# ALU.net
KiCad netlist of a schematic drawn in EAGLE
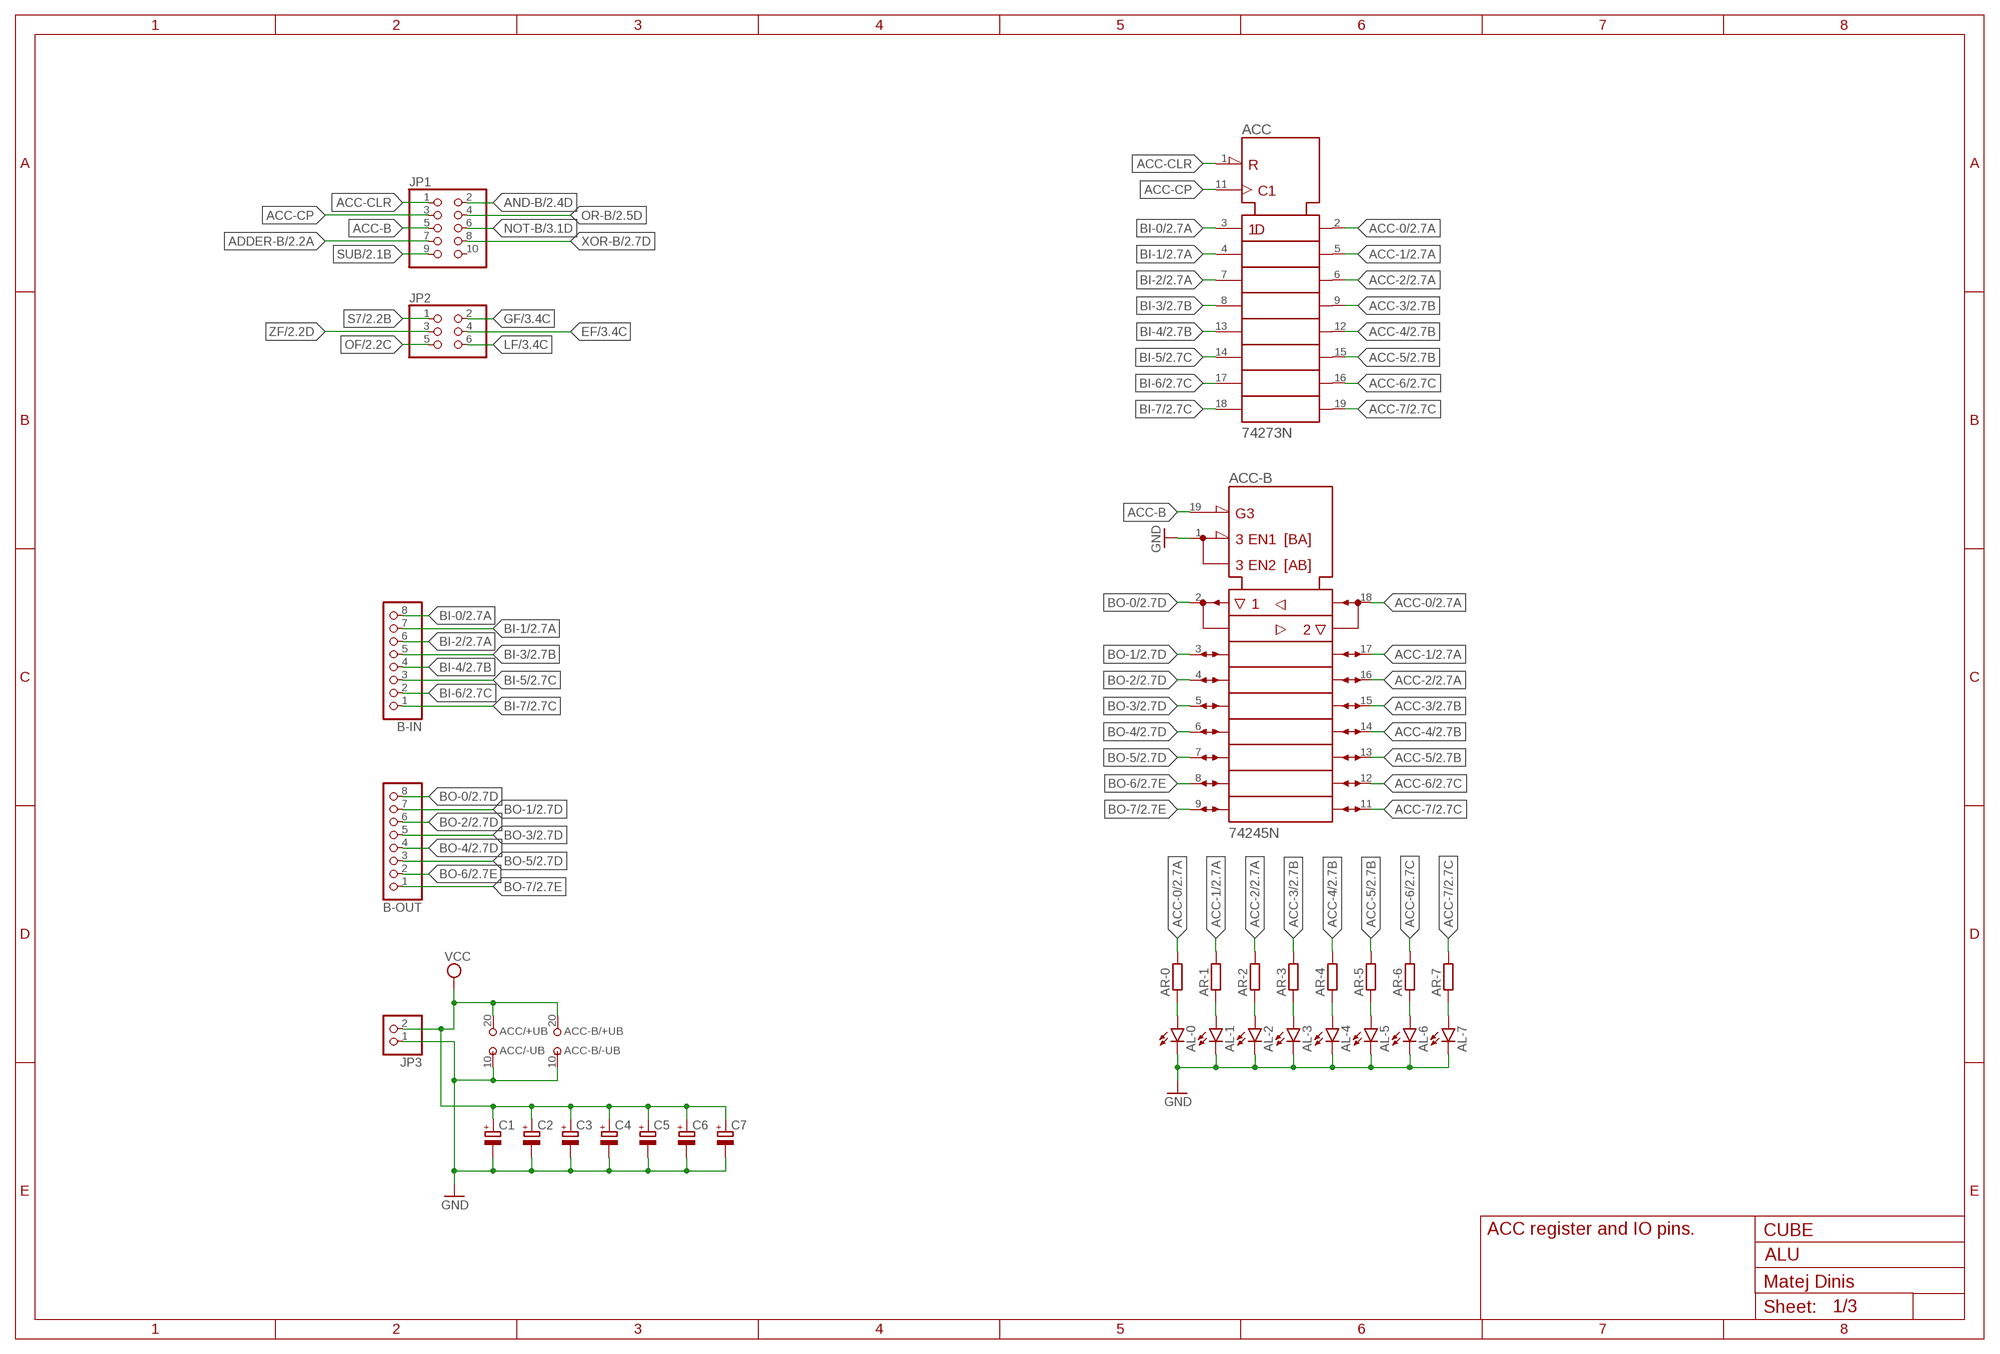
[diagram p0: schematic, sheet 1]
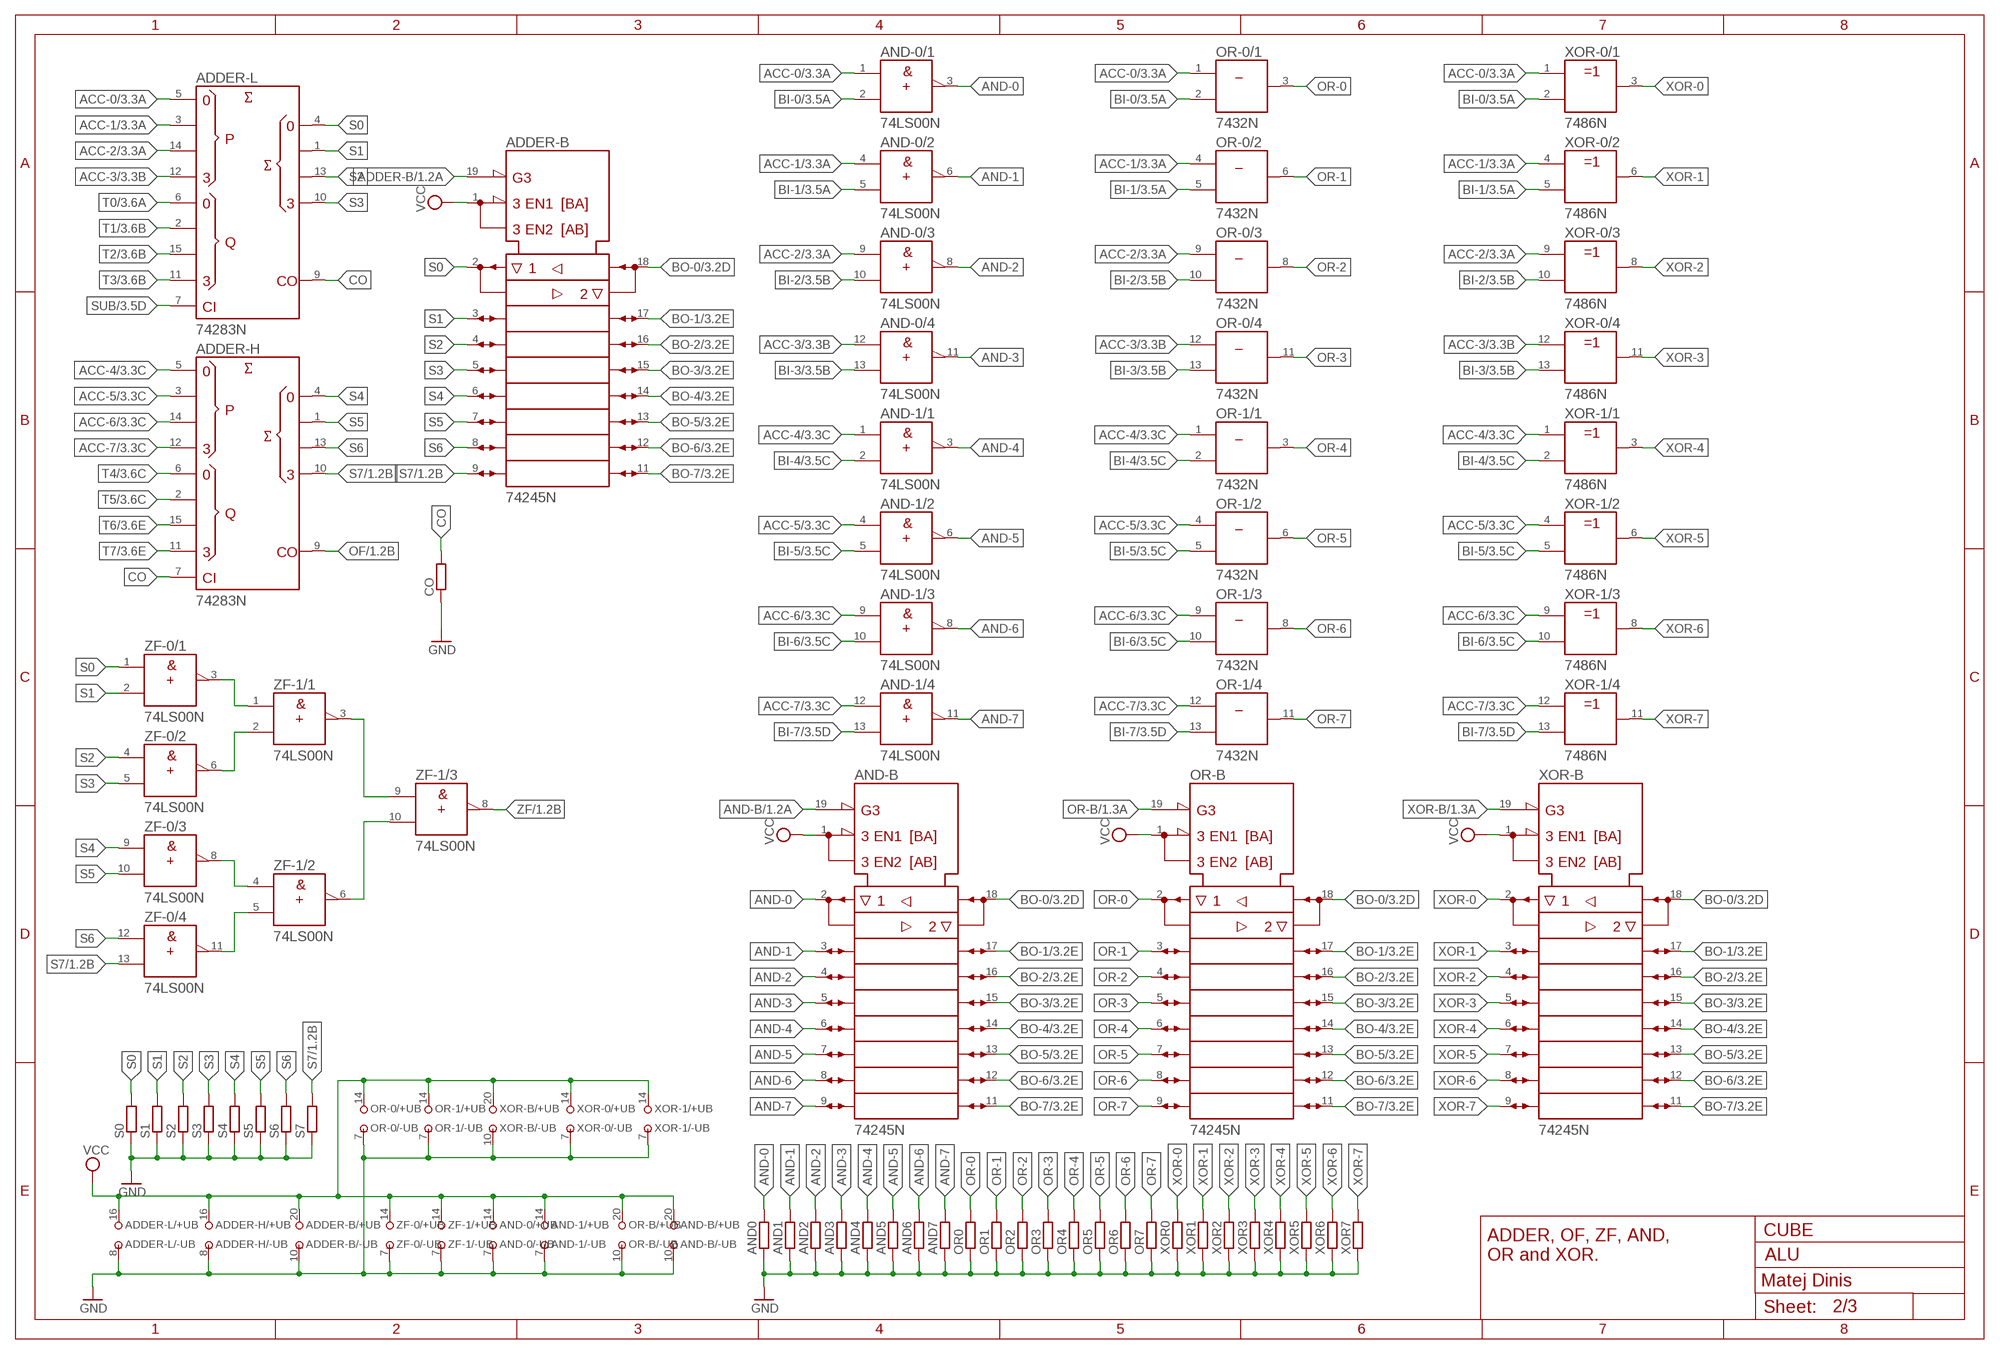
[diagram p1: schematic, sheet 2]
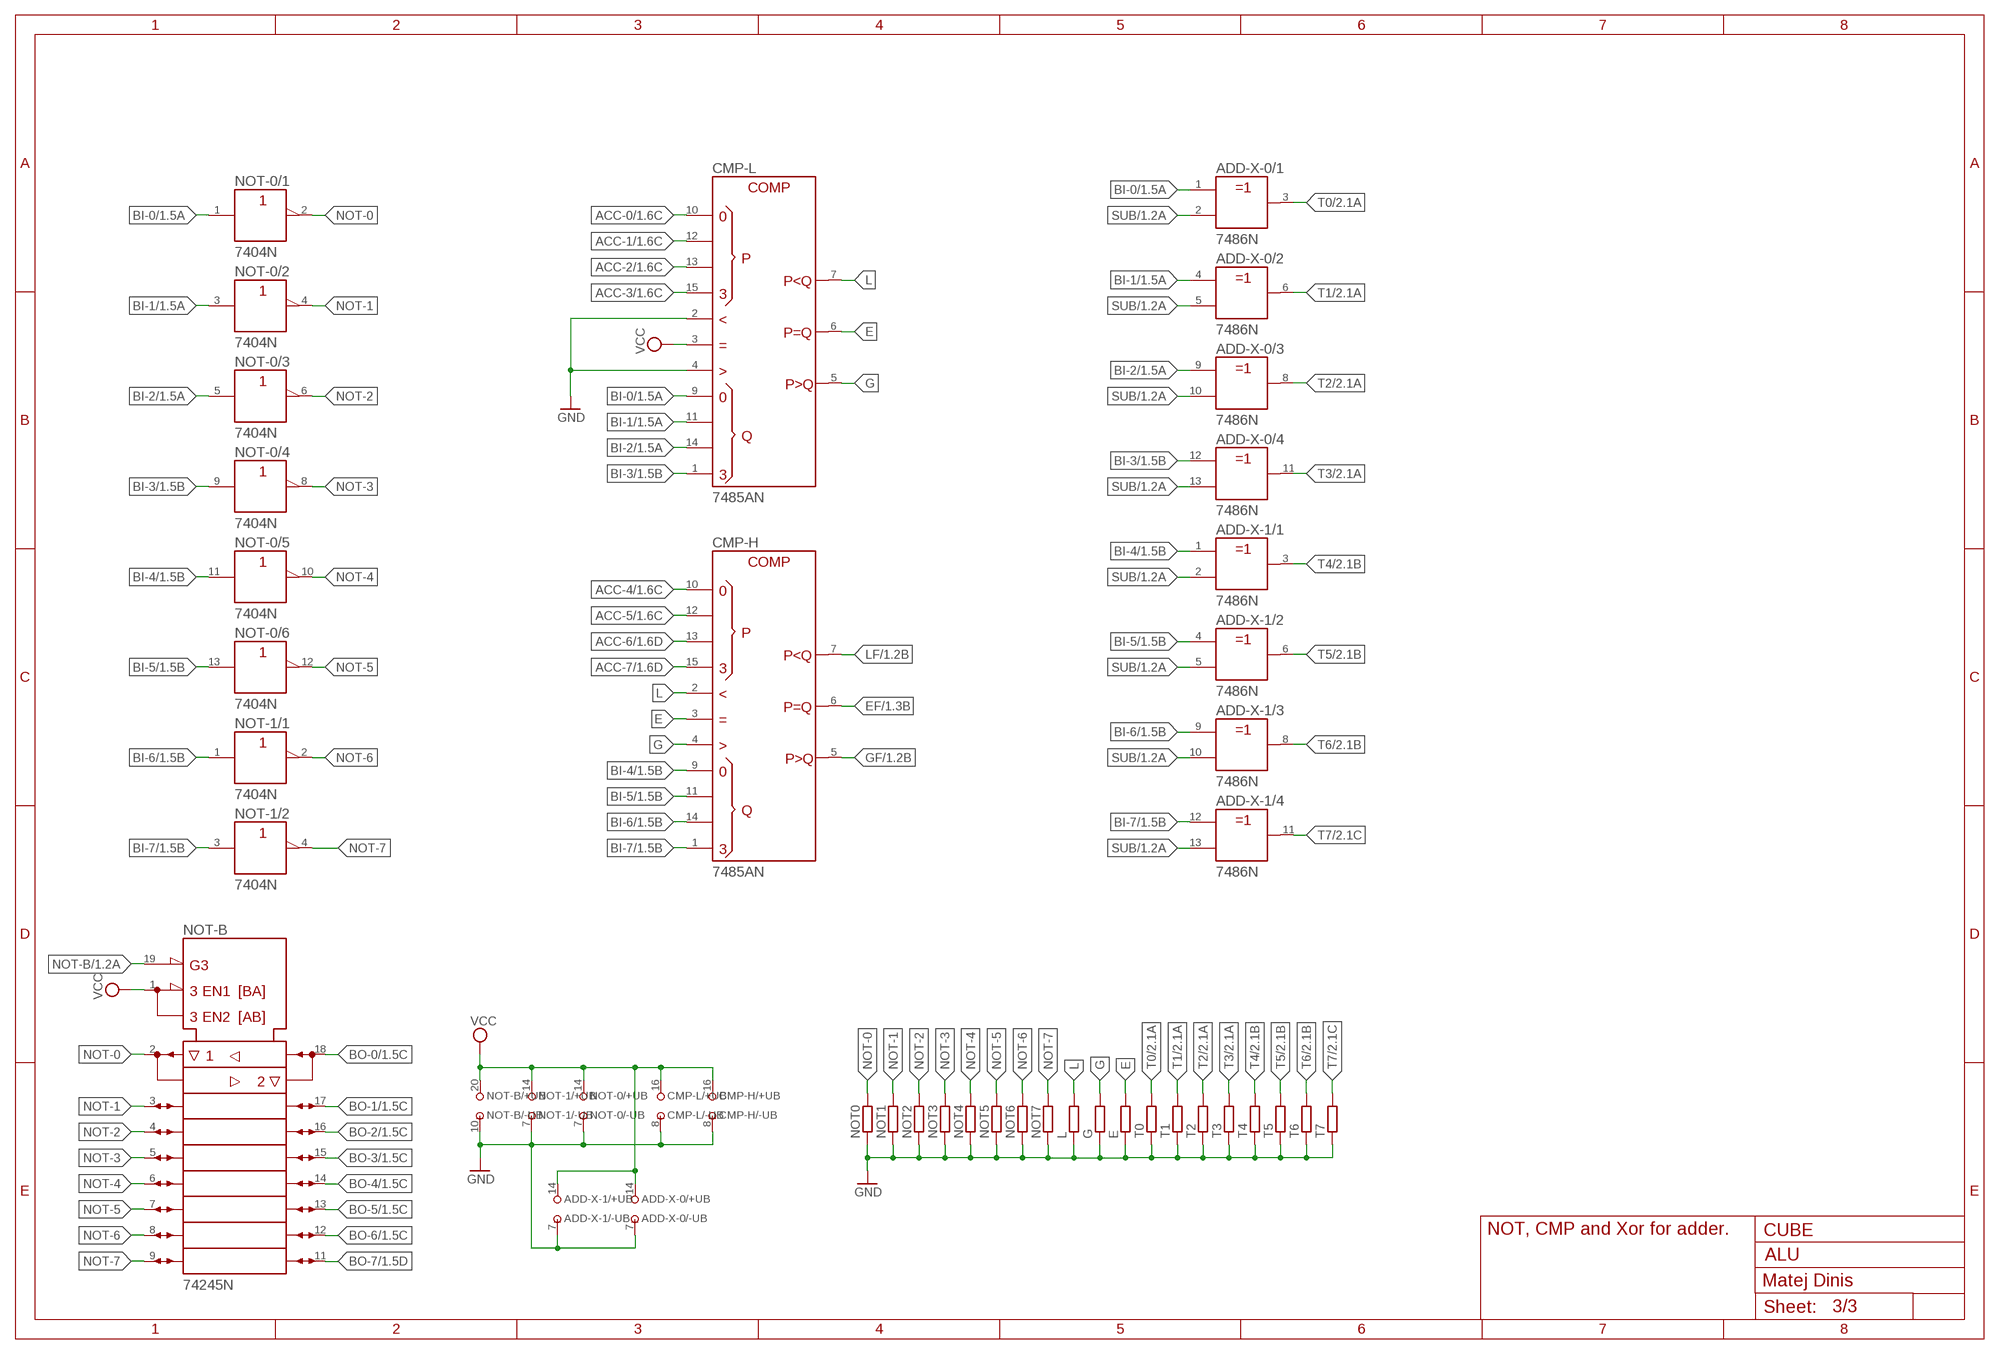
[diagram p2: schematic, sheet 3]

(export (version "E")
  (design (tool "Eeschema 10.0.6"))
  (components
    (comp (ref "ADDER-B")
      (value "74245N")
      (footprint "eagle-import:DIL20")
      (libsource (lib "eagle-import") (part "74245N"))
    )
    (comp (ref "ADDER-H")
      (value "74283N")
      (footprint "eagle-import:DIL16")
      (libsource (lib "eagle-import") (part "74283N"))
    )
    (comp (ref "ADDER-L")
      (value "74283N")
      (footprint "eagle-import:DIL16")
      (libsource (lib "eagle-import") (part "74283N"))
    )
    (comp (ref "AND-0")
      (value "74LS00N")
      (footprint "eagle-import:DIL14")
      (libsource (lib "eagle-import") (part "7400NLS"))
    )
    (comp (ref "AND-1")
      (value "74LS00N")
      (footprint "eagle-import:DIL14")
      (libsource (lib "eagle-import") (part "7400NLS"))
    )
    (comp (ref "AND-B")
      (value "74245N")
      (footprint "eagle-import:DIL20")
      (libsource (lib "eagle-import") (part "74245N"))
    )
    (comp (ref "AND0")
      (value "R-EU_0207/10")
      (footprint "eagle-import:0207_10")
      (libsource (lib "eagle-import") (part "R-EU_0207/10"))
    )
    (comp (ref "AND1")
      (value "R-EU_0207/10")
      (footprint "eagle-import:0207_10")
      (libsource (lib "eagle-import") (part "R-EU_0207/10"))
    )
    (comp (ref "AND2")
      (value "R-EU_0207/10")
      (footprint "eagle-import:0207_10")
      (libsource (lib "eagle-import") (part "R-EU_0207/10"))
    )
    (comp (ref "AND3")
      (value "R-EU_0207/10")
      (footprint "eagle-import:0207_10")
      (libsource (lib "eagle-import") (part "R-EU_0207/10"))
    )
    (comp (ref "AND4")
      (value "R-EU_0207/10")
      (footprint "eagle-import:0207_10")
      (libsource (lib "eagle-import") (part "R-EU_0207/10"))
    )
    (comp (ref "AND5")
      (value "R-EU_0207/10")
      (footprint "eagle-import:0207_10")
      (libsource (lib "eagle-import") (part "R-EU_0207/10"))
    )
    (comp (ref "AND6")
      (value "R-EU_0207/10")
      (footprint "eagle-import:0207_10")
      (libsource (lib "eagle-import") (part "R-EU_0207/10"))
    )
    (comp (ref "AND7")
      (value "R-EU_0207/10")
      (footprint "eagle-import:0207_10")
      (libsource (lib "eagle-import") (part "R-EU_0207/10"))
    )
    (comp (ref "CO")
      (value "R-EU_0207/10")
      (footprint "eagle-import:0207_10")
      (libsource (lib "eagle-import") (part "R-EU_0207/10"))
    )
    (comp (ref "OR-0")
      (value "7432N")
      (footprint "eagle-import:DIL14")
      (libsource (lib "eagle-import") (part "7432N"))
    )
    (comp (ref "OR-1")
      (value "7432N")
      (footprint "eagle-import:DIL14")
      (libsource (lib "eagle-import") (part "7432N"))
    )
    (comp (ref "OR-B")
      (value "74245N")
      (footprint "eagle-import:DIL20")
      (libsource (lib "eagle-import") (part "74245N"))
    )
    (comp (ref "OR0")
      (value "R-EU_0207/10")
      (footprint "eagle-import:0207_10")
      (libsource (lib "eagle-import") (part "R-EU_0207/10"))
    )
    (comp (ref "OR1")
      (value "R-EU_0207/10")
      (footprint "eagle-import:0207_10")
      (libsource (lib "eagle-import") (part "R-EU_0207/10"))
    )
    (comp (ref "OR2")
      (value "R-EU_0207/10")
      (footprint "eagle-import:0207_10")
      (libsource (lib "eagle-import") (part "R-EU_0207/10"))
    )
    (comp (ref "OR3")
      (value "R-EU_0207/10")
      (footprint "eagle-import:0207_10")
      (libsource (lib "eagle-import") (part "R-EU_0207/10"))
    )
    (comp (ref "OR4")
      (value "R-EU_0207/10")
      (footprint "eagle-import:0207_10")
      (libsource (lib "eagle-import") (part "R-EU_0207/10"))
    )
    (comp (ref "OR5")
      (value "R-EU_0207/10")
      (footprint "eagle-import:0207_10")
      (libsource (lib "eagle-import") (part "R-EU_0207/10"))
    )
    (comp (ref "OR6")
      (value "R-EU_0207/10")
      (footprint "eagle-import:0207_10")
      (libsource (lib "eagle-import") (part "R-EU_0207/10"))
    )
    (comp (ref "OR7")
      (value "R-EU_0207/10")
      (footprint "eagle-import:0207_10")
      (libsource (lib "eagle-import") (part "R-EU_0207/10"))
    )
    (comp (ref "S0")
      (value "R-EU_0207/10")
      (footprint "eagle-import:0207_10")
      (libsource (lib "eagle-import") (part "R-EU_0207/10"))
    )
    (comp (ref "S1")
      (value "R-EU_0207/10")
      (footprint "eagle-import:0207_10")
      (libsource (lib "eagle-import") (part "R-EU_0207/10"))
    )
    (comp (ref "S2")
      (value "R-EU_0207/10")
      (footprint "eagle-import:0207_10")
      (libsource (lib "eagle-import") (part "R-EU_0207/10"))
    )
    (comp (ref "S3")
      (value "R-EU_0207/10")
      (footprint "eagle-import:0207_10")
      (libsource (lib "eagle-import") (part "R-EU_0207/10"))
    )
    (comp (ref "S4")
      (value "R-EU_0207/10")
      (footprint "eagle-import:0207_10")
      (libsource (lib "eagle-import") (part "R-EU_0207/10"))
    )
    (comp (ref "S5")
      (value "R-EU_0207/10")
      (footprint "eagle-import:0207_10")
      (libsource (lib "eagle-import") (part "R-EU_0207/10"))
    )
    (comp (ref "S6")
      (value "R-EU_0207/10")
      (footprint "eagle-import:0207_10")
      (libsource (lib "eagle-import") (part "R-EU_0207/10"))
    )
    (comp (ref "S7")
      (value "R-EU_0207/10")
      (footprint "eagle-import:0207_10")
      (libsource (lib "eagle-import") (part "R-EU_0207/10"))
    )
    (comp (ref "XOR-0")
      (value "7486N")
      (footprint "eagle-import:DIL14")
      (libsource (lib "eagle-import") (part "7486N"))
    )
    (comp (ref "XOR-1")
      (value "7486N")
      (footprint "eagle-import:DIL14")
      (libsource (lib "eagle-import") (part "7486N"))
    )
    (comp (ref "XOR-B")
      (value "74245N")
      (footprint "eagle-import:DIL20")
      (libsource (lib "eagle-import") (part "74245N"))
    )
    (comp (ref "XOR0")
      (value "R-EU_0207/10")
      (footprint "eagle-import:0207_10")
      (libsource (lib "eagle-import") (part "R-EU_0207/10"))
    )
    (comp (ref "XOR1")
      (value "R-EU_0207/10")
      (footprint "eagle-import:0207_10")
      (libsource (lib "eagle-import") (part "R-EU_0207/10"))
    )
    (comp (ref "XOR2")
      (value "R-EU_0207/10")
      (footprint "eagle-import:0207_10")
      (libsource (lib "eagle-import") (part "R-EU_0207/10"))
    )
    (comp (ref "XOR3")
      (value "R-EU_0207/10")
      (footprint "eagle-import:0207_10")
      (libsource (lib "eagle-import") (part "R-EU_0207/10"))
    )
    (comp (ref "XOR4")
      (value "R-EU_0207/10")
      (footprint "eagle-import:0207_10")
      (libsource (lib "eagle-import") (part "R-EU_0207/10"))
    )
    (comp (ref "XOR5")
      (value "R-EU_0207/10")
      (footprint "eagle-import:0207_10")
      (libsource (lib "eagle-import") (part "R-EU_0207/10"))
    )
    (comp (ref "XOR6")
      (value "R-EU_0207/10")
      (footprint "eagle-import:0207_10")
      (libsource (lib "eagle-import") (part "R-EU_0207/10"))
    )
    (comp (ref "XOR7")
      (value "R-EU_0207/10")
      (footprint "eagle-import:0207_10")
      (libsource (lib "eagle-import") (part "R-EU_0207/10"))
    )
    (comp (ref "ZF-0")
      (value "74LS00N")
      (footprint "eagle-import:DIL14")
      (libsource (lib "eagle-import") (part "7400NLS"))
    )
    (comp (ref "ZF-1")
      (value "74LS00N")
      (footprint "eagle-import:DIL14")
      (libsource (lib "eagle-import") (part "7400NLS"))
    )
    (comp (ref "ADD-X-0")
      (value "7486N")
      (footprint "eagle-import:DIL14")
      (libsource (lib "eagle-import") (part "7486N"))
    )
    (comp (ref "ADD-X-1")
      (value "7486N")
      (footprint "eagle-import:DIL14")
      (libsource (lib "eagle-import") (part "7486N"))
    )
    (comp (ref "CMP-H")
      (value "7485AN")
      (footprint "eagle-import:DIL16")
      (libsource (lib "eagle-import") (part "7485AN"))
    )
    (comp (ref "CMP-L")
      (value "7485AN")
      (footprint "eagle-import:DIL16")
      (libsource (lib "eagle-import") (part "7485AN"))
    )
    (comp (ref "E")
      (value "R-EU_0207/10")
      (footprint "eagle-import:0207_10")
      (libsource (lib "eagle-import") (part "R-EU_0207/10"))
    )
    (comp (ref "G")
      (value "R-EU_0207/10")
      (footprint "eagle-import:0207_10")
      (libsource (lib "eagle-import") (part "R-EU_0207/10"))
    )
    (comp (ref "L")
      (value "R-EU_0207/10")
      (footprint "eagle-import:0207_10")
      (libsource (lib "eagle-import") (part "R-EU_0207/10"))
    )
    (comp (ref "NOT-0")
      (value "7404N")
      (footprint "eagle-import:DIL14")
      (libsource (lib "eagle-import") (part "7404N"))
    )
    (comp (ref "NOT-1")
      (value "7404N")
      (footprint "eagle-import:DIL14")
      (libsource (lib "eagle-import") (part "7404N"))
    )
    (comp (ref "NOT-B")
      (value "74245N")
      (footprint "eagle-import:DIL20")
      (libsource (lib "eagle-import") (part "74245N"))
    )
    (comp (ref "NOT0")
      (value "R-EU_0207/10")
      (footprint "eagle-import:0207_10")
      (libsource (lib "eagle-import") (part "R-EU_0207/10"))
    )
    (comp (ref "NOT1")
      (value "R-EU_0207/10")
      (footprint "eagle-import:0207_10")
      (libsource (lib "eagle-import") (part "R-EU_0207/10"))
    )
    (comp (ref "NOT2")
      (value "R-EU_0207/10")
      (footprint "eagle-import:0207_10")
      (libsource (lib "eagle-import") (part "R-EU_0207/10"))
    )
    (comp (ref "NOT3")
      (value "R-EU_0207/10")
      (footprint "eagle-import:0207_10")
      (libsource (lib "eagle-import") (part "R-EU_0207/10"))
    )
    (comp (ref "NOT4")
      (value "R-EU_0207/10")
      (footprint "eagle-import:0207_10")
      (libsource (lib "eagle-import") (part "R-EU_0207/10"))
    )
    (comp (ref "NOT5")
      (value "R-EU_0207/10")
      (footprint "eagle-import:0207_10")
      (libsource (lib "eagle-import") (part "R-EU_0207/10"))
    )
    (comp (ref "NOT6")
      (value "R-EU_0207/10")
      (footprint "eagle-import:0207_10")
      (libsource (lib "eagle-import") (part "R-EU_0207/10"))
    )
    (comp (ref "NOT7")
      (value "R-EU_0207/10")
      (footprint "eagle-import:0207_10")
      (libsource (lib "eagle-import") (part "R-EU_0207/10"))
    )
    (comp (ref "T0")
      (value "R-EU_0207/10")
      (footprint "eagle-import:0207_10")
      (libsource (lib "eagle-import") (part "R-EU_0207/10"))
    )
    (comp (ref "T1")
      (value "R-EU_0207/10")
      (footprint "eagle-import:0207_10")
      (libsource (lib "eagle-import") (part "R-EU_0207/10"))
    )
    (comp (ref "T2")
      (value "R-EU_0207/10")
      (footprint "eagle-import:0207_10")
      (libsource (lib "eagle-import") (part "R-EU_0207/10"))
    )
    (comp (ref "T3")
      (value "R-EU_0207/10")
      (footprint "eagle-import:0207_10")
      (libsource (lib "eagle-import") (part "R-EU_0207/10"))
    )
    (comp (ref "T4")
      (value "R-EU_0207/10")
      (footprint "eagle-import:0207_10")
      (libsource (lib "eagle-import") (part "R-EU_0207/10"))
    )
    (comp (ref "T5")
      (value "R-EU_0207/10")
      (footprint "eagle-import:0207_10")
      (libsource (lib "eagle-import") (part "R-EU_0207/10"))
    )
    (comp (ref "T6")
      (value "R-EU_0207/10")
      (footprint "eagle-import:0207_10")
      (libsource (lib "eagle-import") (part "R-EU_0207/10"))
    )
    (comp (ref "T7")
      (value "R-EU_0207/10")
      (footprint "eagle-import:0207_10")
      (libsource (lib "eagle-import") (part "R-EU_0207/10"))
    )
    (comp (ref "ACC")
      (value "74273N")
      (footprint "eagle-import:DIL20")
      (libsource (lib "eagle-import") (part "74273N"))
    )
    (comp (ref "ACC-B")
      (value "74245N")
      (footprint "eagle-import:DIL20")
      (libsource (lib "eagle-import") (part "74245N"))
    )
    (comp (ref "AL-0")
      (value "LED5MM")
      (footprint "eagle-import:LED5MM")
      (libsource (lib "eagle-import") (part "LED5MM"))
    )
    (comp (ref "AL-1")
      (value "LED5MM")
      (footprint "eagle-import:LED5MM")
      (libsource (lib "eagle-import") (part "LED5MM"))
    )
    (comp (ref "AL-2")
      (value "LED5MM")
      (footprint "eagle-import:LED5MM")
      (libsource (lib "eagle-import") (part "LED5MM"))
    )
    (comp (ref "AL-3")
      (value "LED5MM")
      (footprint "eagle-import:LED5MM")
      (libsource (lib "eagle-import") (part "LED5MM"))
    )
    (comp (ref "AL-4")
      (value "LED5MM")
      (footprint "eagle-import:LED5MM")
      (libsource (lib "eagle-import") (part "LED5MM"))
    )
    (comp (ref "AL-5")
      (value "LED5MM")
      (footprint "eagle-import:LED5MM")
      (libsource (lib "eagle-import") (part "LED5MM"))
    )
    (comp (ref "AL-6")
      (value "LED5MM")
      (footprint "eagle-import:LED5MM")
      (libsource (lib "eagle-import") (part "LED5MM"))
    )
    (comp (ref "AL-7")
      (value "LED5MM")
      (footprint "eagle-import:LED5MM")
      (libsource (lib "eagle-import") (part "LED5MM"))
    )
    (comp (ref "AR-0")
      (value "R-EU_0207/10")
      (footprint "eagle-import:0207_10")
      (libsource (lib "eagle-import") (part "R-EU_0207/10"))
    )
    (comp (ref "AR-1")
      (value "R-EU_0207/10")
      (footprint "eagle-import:0207_10")
      (libsource (lib "eagle-import") (part "R-EU_0207/10"))
    )
    (comp (ref "AR-2")
      (value "R-EU_0207/10")
      (footprint "eagle-import:0207_10")
      (libsource (lib "eagle-import") (part "R-EU_0207/10"))
    )
    (comp (ref "AR-3")
      (value "R-EU_0207/10")
      (footprint "eagle-import:0207_10")
      (libsource (lib "eagle-import") (part "R-EU_0207/10"))
    )
    (comp (ref "AR-4")
      (value "R-EU_0207/10")
      (footprint "eagle-import:0207_10")
      (libsource (lib "eagle-import") (part "R-EU_0207/10"))
    )
    (comp (ref "AR-5")
      (value "R-EU_0207/10")
      (footprint "eagle-import:0207_10")
      (libsource (lib "eagle-import") (part "R-EU_0207/10"))
    )
    (comp (ref "AR-6")
      (value "R-EU_0207/10")
      (footprint "eagle-import:0207_10")
      (libsource (lib "eagle-import") (part "R-EU_0207/10"))
    )
    (comp (ref "AR-7")
      (value "R-EU_0207/10")
      (footprint "eagle-import:0207_10")
      (libsource (lib "eagle-import") (part "R-EU_0207/10"))
    )
    (comp (ref "B-IN")
      (value "PINHD-1X8")
      (footprint "eagle-import:1X08")
      (libsource (lib "eagle-import") (part "PINHD-1X8"))
    )
    (comp (ref "B-OUT")
      (value "PINHD-1X8")
      (footprint "eagle-import:1X08")
      (libsource (lib "eagle-import") (part "PINHD-1X8"))
    )
    (comp (ref "C1")
      (value "CPOL-EUE3.5-8")
      (footprint "eagle-import:E3,5-8")
      (libsource (lib "eagle-import") (part "CPOL-EUE3.5-8"))
    )
    (comp (ref "C2")
      (value "CPOL-EUE3.5-8")
      (footprint "eagle-import:E3,5-8")
      (libsource (lib "eagle-import") (part "CPOL-EUE3.5-8"))
    )
    (comp (ref "C3")
      (value "CPOL-EUE3.5-8")
      (footprint "eagle-import:E3,5-8")
      (libsource (lib "eagle-import") (part "CPOL-EUE3.5-8"))
    )
    (comp (ref "C4")
      (value "CPOL-EUE3.5-8")
      (footprint "eagle-import:E3,5-8")
      (libsource (lib "eagle-import") (part "CPOL-EUE3.5-8"))
    )
    (comp (ref "C5")
      (value "CPOL-EUE3.5-8")
      (footprint "eagle-import:E3,5-8")
      (libsource (lib "eagle-import") (part "CPOL-EUE3.5-8"))
    )
    (comp (ref "C6")
      (value "CPOL-EUE3.5-8")
      (footprint "eagle-import:E3,5-8")
      (libsource (lib "eagle-import") (part "CPOL-EUE3.5-8"))
    )
    (comp (ref "C7")
      (value "CPOL-EUE3.5-8")
      (footprint "eagle-import:E3,5-8")
      (libsource (lib "eagle-import") (part "CPOL-EUE3.5-8"))
    )
    (comp (ref "JP1")
      (value "PINHD-2X5")
      (footprint "eagle-import:2X05")
      (libsource (lib "eagle-import") (part "PINHD-2X5"))
    )
    (comp (ref "JP2")
      (value "PINHD-2X3")
      (footprint "eagle-import:2X03")
      (libsource (lib "eagle-import") (part "PINHD-2X3"))
    )
    (comp (ref "JP3")
      (value "PINHD-1X2")
      (footprint "eagle-import:1X02")
      (libsource (lib "eagle-import") (part "PINHD-1X2"))
    )
  )
  (nets
    (net (code "1") (name "ACC-0") (class "Default")
      (node (ref "ACC") (pin "2") (pinfunction "1Q_2") (pintype "output"))
      (node (ref "ACC-B") (pin "18") (pinfunction "B1_18") (pintype "bidirectional"))
      (node (ref "ADDER-L") (pin "5") (pinfunction "A1_5") (pintype "input"))
      (node (ref "AND-0") (pin "1") (pinfunction "A_1") (pintype "input"))
      (node (ref "AR-0") (pin "2") (pinfunction "2_2") (pintype "passive"))
      (node (ref "CMP-L") (pin "10") (pinfunction "P0_10") (pintype "input"))
      (node (ref "OR-0") (pin "1") (pinfunction "A_1") (pintype "input"))
      (node (ref "XOR-0") (pin "1") (pinfunction "A_1") (pintype "input"))
    )
    (net (code "2") (name "ACC-1") (class "Default")
      (node (ref "ACC") (pin "5") (pinfunction "2Q_5") (pintype "output"))
      (node (ref "ACC-B") (pin "17") (pinfunction "B2_17") (pintype "bidirectional"))
      (node (ref "ADDER-L") (pin "3") (pinfunction "A2_3") (pintype "input"))
      (node (ref "AND-0") (pin "4") (pinfunction "A_4") (pintype "input"))
      (node (ref "AR-1") (pin "2") (pinfunction "2_2") (pintype "passive"))
      (node (ref "CMP-L") (pin "12") (pinfunction "P1_12") (pintype "input"))
      (node (ref "OR-0") (pin "4") (pinfunction "A_4") (pintype "input"))
      (node (ref "XOR-0") (pin "4") (pinfunction "A_4") (pintype "input"))
    )
    (net (code "3") (name "ACC-2") (class "Default")
      (node (ref "ACC") (pin "6") (pinfunction "3Q_6") (pintype "output"))
      (node (ref "ACC-B") (pin "16") (pinfunction "B3_16") (pintype "bidirectional"))
      (node (ref "ADDER-L") (pin "14") (pinfunction "A3_14") (pintype "input"))
      (node (ref "AND-0") (pin "9") (pinfunction "A_9") (pintype "input"))
      (node (ref "AR-2") (pin "2") (pinfunction "2_2") (pintype "passive"))
      (node (ref "CMP-L") (pin "13") (pinfunction "P2_13") (pintype "input"))
      (node (ref "OR-0") (pin "9") (pinfunction "A_9") (pintype "input"))
      (node (ref "XOR-0") (pin "9") (pinfunction "A_9") (pintype "input"))
    )
    (net (code "4") (name "ACC-3") (class "Default")
      (node (ref "ACC") (pin "9") (pinfunction "4Q_9") (pintype "output"))
      (node (ref "ACC-B") (pin "15") (pinfunction "B4_15") (pintype "bidirectional"))
      (node (ref "ADDER-L") (pin "12") (pinfunction "A4_12") (pintype "input"))
      (node (ref "AND-0") (pin "12") (pinfunction "A_12") (pintype "input"))
      (node (ref "AR-3") (pin "2") (pinfunction "2_2") (pintype "passive"))
      (node (ref "CMP-L") (pin "15") (pinfunction "P3_15") (pintype "input"))
      (node (ref "OR-0") (pin "12") (pinfunction "A_12") (pintype "input"))
      (node (ref "XOR-0") (pin "12") (pinfunction "A_12") (pintype "input"))
    )
    (net (code "5") (name "ACC-4") (class "Default")
      (node (ref "ACC") (pin "12") (pinfunction "5Q_12") (pintype "output"))
      (node (ref "ACC-B") (pin "14") (pinfunction "B5_14") (pintype "bidirectional"))
      (node (ref "ADDER-H") (pin "5") (pinfunction "A1_5") (pintype "input"))
      (node (ref "AND-1") (pin "1") (pinfunction "A_1") (pintype "input"))
      (node (ref "AR-4") (pin "2") (pinfunction "2_2") (pintype "passive"))
      (node (ref "CMP-H") (pin "10") (pinfunction "P0_10") (pintype "input"))
      (node (ref "OR-1") (pin "1") (pinfunction "A_1") (pintype "input"))
      (node (ref "XOR-1") (pin "1") (pinfunction "A_1") (pintype "input"))
    )
    (net (code "6") (name "ACC-5") (class "Default")
      (node (ref "ACC") (pin "15") (pinfunction "6Q_15") (pintype "output"))
      (node (ref "ACC-B") (pin "13") (pinfunction "B6_13") (pintype "bidirectional"))
      (node (ref "ADDER-H") (pin "3") (pinfunction "A2_3") (pintype "input"))
      (node (ref "AND-1") (pin "4") (pinfunction "A_4") (pintype "input"))
      (node (ref "AR-5") (pin "2") (pinfunction "2_2") (pintype "passive"))
      (node (ref "CMP-H") (pin "12") (pinfunction "P1_12") (pintype "input"))
      (node (ref "OR-1") (pin "4") (pinfunction "A_4") (pintype "input"))
      (node (ref "XOR-1") (pin "4") (pinfunction "A_4") (pintype "input"))
    )
    (net (code "7") (name "ACC-6") (class "Default")
      (node (ref "ACC") (pin "16") (pinfunction "7Q_16") (pintype "output"))
      (node (ref "ACC-B") (pin "12") (pinfunction "B7_12") (pintype "bidirectional"))
      (node (ref "ADDER-H") (pin "14") (pinfunction "A3_14") (pintype "input"))
      (node (ref "AND-1") (pin "9") (pinfunction "A_9") (pintype "input"))
      (node (ref "AR-6") (pin "2") (pinfunction "2_2") (pintype "passive"))
      (node (ref "CMP-H") (pin "13") (pinfunction "P2_13") (pintype "input"))
      (node (ref "OR-1") (pin "9") (pinfunction "A_9") (pintype "input"))
      (node (ref "XOR-1") (pin "9") (pinfunction "A_9") (pintype "input"))
    )
    (net (code "8") (name "ACC-7") (class "Default")
      (node (ref "ACC") (pin "19") (pinfunction "8Q_19") (pintype "output"))
      (node (ref "ACC-B") (pin "11") (pinfunction "B8_11") (pintype "bidirectional"))
      (node (ref "ADDER-H") (pin "12") (pinfunction "A4_12") (pintype "input"))
      (node (ref "AND-1") (pin "12") (pinfunction "A_12") (pintype "input"))
      (node (ref "AR-7") (pin "2") (pinfunction "2_2") (pintype "passive"))
      (node (ref "CMP-H") (pin "15") (pinfunction "P3_15") (pintype "input"))
      (node (ref "OR-1") (pin "12") (pinfunction "A_12") (pintype "input"))
      (node (ref "XOR-1") (pin "12") (pinfunction "A_12") (pintype "input"))
    )
    (net (code "9") (name "ACC-B") (class "Default")
      (node (ref "ACC-B") (pin "19") (pinfunction "~{G}_19") (pintype "input"))
      (node (ref "JP1") (pin "5") (pinfunction "5_5") (pintype "passive"))
    )
    (net (code "10") (name "ACC-CLR") (class "Default")
      (node (ref "ACC") (pin "1") (pinfunction "~{CLR}_1") (pintype "input"))
      (node (ref "JP1") (pin "1") (pinfunction "1_1") (pintype "passive"))
    )
    (net (code "11") (name "ACC-CP") (class "Default")
      (node (ref "ACC") (pin "11") (pinfunction "CLK_11") (pintype "input"))
      (node (ref "JP1") (pin "3") (pinfunction "3_3") (pintype "passive"))
    )
    (net (code "12") (name "ADDER-B") (class "Default")
      (node (ref "ADDER-B") (pin "19") (pinfunction "~{G}_19") (pintype "input"))
      (node (ref "JP1") (pin "7") (pinfunction "7_7") (pintype "passive"))
    )
    (net (code "13") (name "AND-0") (class "Default")
      (node (ref "AND-0") (pin "3") (pinfunction "Y_3") (pintype "output"))
      (node (ref "AND-B") (pin "2") (pinfunction "A1_2") (pintype "bidirectional"))
      (node (ref "AND0") (pin "2") (pinfunction "2_2") (pintype "passive"))
    )
    (net (code "14") (name "AND-1") (class "Default")
      (node (ref "AND-0") (pin "6") (pinfunction "Y_6") (pintype "output"))
      (node (ref "AND-B") (pin "3") (pinfunction "A2_3") (pintype "bidirectional"))
      (node (ref "AND1") (pin "2") (pinfunction "2_2") (pintype "passive"))
    )
    (net (code "15") (name "AND-2") (class "Default")
      (node (ref "AND-0") (pin "8") (pinfunction "Y_8") (pintype "output"))
      (node (ref "AND-B") (pin "4") (pinfunction "A3_4") (pintype "bidirectional"))
      (node (ref "AND2") (pin "2") (pinfunction "2_2") (pintype "passive"))
    )
    (net (code "16") (name "AND-3") (class "Default")
      (node (ref "AND-0") (pin "11") (pinfunction "Y_11") (pintype "output"))
      (node (ref "AND-B") (pin "5") (pinfunction "A4_5") (pintype "bidirectional"))
      (node (ref "AND3") (pin "2") (pinfunction "2_2") (pintype "passive"))
    )
    (net (code "17") (name "AND-4") (class "Default")
      (node (ref "AND-1") (pin "3") (pinfunction "Y_3") (pintype "output"))
      (node (ref "AND-B") (pin "6") (pinfunction "A5_6") (pintype "bidirectional"))
      (node (ref "AND4") (pin "2") (pinfunction "2_2") (pintype "passive"))
    )
    (net (code "18") (name "AND-5") (class "Default")
      (node (ref "AND-1") (pin "6") (pinfunction "Y_6") (pintype "output"))
      (node (ref "AND-B") (pin "7") (pinfunction "A6_7") (pintype "bidirectional"))
      (node (ref "AND5") (pin "2") (pinfunction "2_2") (pintype "passive"))
    )
    (net (code "19") (name "AND-6") (class "Default")
      (node (ref "AND-1") (pin "8") (pinfunction "Y_8") (pintype "output"))
      (node (ref "AND-B") (pin "8") (pinfunction "A7_8") (pintype "bidirectional"))
      (node (ref "AND6") (pin "2") (pinfunction "2_2") (pintype "passive"))
    )
    (net (code "20") (name "AND-7") (class "Default")
      (node (ref "AND-1") (pin "11") (pinfunction "Y_11") (pintype "output"))
      (node (ref "AND-B") (pin "9") (pinfunction "A8_9") (pintype "bidirectional"))
      (node (ref "AND7") (pin "2") (pinfunction "2_2") (pintype "passive"))
    )
    (net (code "21") (name "AND-B") (class "Default")
      (node (ref "AND-B") (pin "19") (pinfunction "~{G}_19") (pintype "input"))
      (node (ref "JP1") (pin "2") (pinfunction "2_2") (pintype "passive"))
    )
    (net (code "22") (name "BI-0") (class "Default")
      (node (ref "ACC") (pin "3") (pinfunction "1D_3") (pintype "input"))
      (node (ref "ADD-X-0") (pin "1") (pinfunction "A_1") (pintype "input"))
      (node (ref "AND-0") (pin "2") (pinfunction "B_2") (pintype "input"))
      (node (ref "B-IN") (pin "8") (pinfunction "8_8") (pintype "passive"))
      (node (ref "CMP-L") (pin "9") (pinfunction "Q0_9") (pintype "input"))
      (node (ref "NOT-0") (pin "1") (pinfunction "A_1") (pintype "input"))
      (node (ref "OR-0") (pin "2") (pinfunction "B_2") (pintype "input"))
      (node (ref "XOR-0") (pin "2") (pinfunction "B_2") (pintype "input"))
    )
    (net (code "23") (name "BI-1") (class "Default")
      (node (ref "ACC") (pin "4") (pinfunction "2D_4") (pintype "input"))
      (node (ref "ADD-X-0") (pin "4") (pinfunction "A_4") (pintype "input"))
      (node (ref "AND-0") (pin "5") (pinfunction "B_5") (pintype "input"))
      (node (ref "B-IN") (pin "7") (pinfunction "7_7") (pintype "passive"))
      (node (ref "CMP-L") (pin "11") (pinfunction "Q1_11") (pintype "input"))
      (node (ref "NOT-0") (pin "3") (pinfunction "A_3") (pintype "input"))
      (node (ref "OR-0") (pin "5") (pinfunction "B_5") (pintype "input"))
      (node (ref "XOR-0") (pin "5") (pinfunction "B_5") (pintype "input"))
    )
    (net (code "24") (name "BI-2") (class "Default")
      (node (ref "ACC") (pin "7") (pinfunction "3D_7") (pintype "input"))
      (node (ref "ADD-X-0") (pin "9") (pinfunction "A_9") (pintype "input"))
      (node (ref "AND-0") (pin "10") (pinfunction "B_10") (pintype "input"))
      (node (ref "B-IN") (pin "6") (pinfunction "6_6") (pintype "passive"))
      (node (ref "CMP-L") (pin "14") (pinfunction "Q2_14") (pintype "input"))
      (node (ref "NOT-0") (pin "5") (pinfunction "A_5") (pintype "input"))
      (node (ref "OR-0") (pin "10") (pinfunction "B_10") (pintype "input"))
      (node (ref "XOR-0") (pin "10") (pinfunction "B_10") (pintype "input"))
    )
    (net (code "25") (name "BI-3") (class "Default")
      (node (ref "ACC") (pin "8") (pinfunction "4D_8") (pintype "input"))
      (node (ref "ADD-X-0") (pin "12") (pinfunction "A_12") (pintype "input"))
      (node (ref "AND-0") (pin "13") (pinfunction "B_13") (pintype "input"))
      (node (ref "B-IN") (pin "5") (pinfunction "5_5") (pintype "passive"))
      (node (ref "CMP-L") (pin "1") (pinfunction "Q3_1") (pintype "input"))
      (node (ref "NOT-0") (pin "9") (pinfunction "A_9") (pintype "input"))
      (node (ref "OR-0") (pin "13") (pinfunction "B_13") (pintype "input"))
      (node (ref "XOR-0") (pin "13") (pinfunction "B_13") (pintype "input"))
    )
    (net (code "26") (name "BI-4") (class "Default")
      (node (ref "ACC") (pin "13") (pinfunction "5D_13") (pintype "input"))
      (node (ref "ADD-X-1") (pin "1") (pinfunction "A_1") (pintype "input"))
      (node (ref "AND-1") (pin "2") (pinfunction "B_2") (pintype "input"))
      (node (ref "B-IN") (pin "4") (pinfunction "4_4") (pintype "passive"))
      (node (ref "CMP-H") (pin "9") (pinfunction "Q0_9") (pintype "input"))
      (node (ref "NOT-0") (pin "11") (pinfunction "A_11") (pintype "input"))
      (node (ref "OR-1") (pin "2") (pinfunction "B_2") (pintype "input"))
      (node (ref "XOR-1") (pin "2") (pinfunction "B_2") (pintype "input"))
    )
    (net (code "27") (name "BI-5") (class "Default")
      (node (ref "ACC") (pin "14") (pinfunction "6D_14") (pintype "input"))
      (node (ref "ADD-X-1") (pin "4") (pinfunction "A_4") (pintype "input"))
      (node (ref "AND-1") (pin "5") (pinfunction "B_5") (pintype "input"))
      (node (ref "B-IN") (pin "3") (pinfunction "3_3") (pintype "passive"))
      (node (ref "CMP-H") (pin "11") (pinfunction "Q1_11") (pintype "input"))
      (node (ref "NOT-0") (pin "13") (pinfunction "A_13") (pintype "input"))
      (node (ref "OR-1") (pin "5") (pinfunction "B_5") (pintype "input"))
      (node (ref "XOR-1") (pin "5") (pinfunction "B_5") (pintype "input"))
    )
    (net (code "28") (name "BI-6") (class "Default")
      (node (ref "ACC") (pin "17") (pinfunction "7D_17") (pintype "input"))
      (node (ref "ADD-X-1") (pin "9") (pinfunction "A_9") (pintype "input"))
      (node (ref "AND-1") (pin "10") (pinfunction "B_10") (pintype "input"))
      (node (ref "B-IN") (pin "2") (pinfunction "2_2") (pintype "passive"))
      (node (ref "CMP-H") (pin "14") (pinfunction "Q2_14") (pintype "input"))
      (node (ref "NOT-1") (pin "1") (pinfunction "A_1") (pintype "input"))
      (node (ref "OR-1") (pin "10") (pinfunction "B_10") (pintype "input"))
      (node (ref "XOR-1") (pin "10") (pinfunction "B_10") (pintype "input"))
    )
    (net (code "29") (name "BI-7") (class "Default")
      (node (ref "ACC") (pin "18") (pinfunction "8D_18") (pintype "input"))
      (node (ref "ADD-X-1") (pin "12") (pinfunction "A_12") (pintype "input"))
      (node (ref "AND-1") (pin "13") (pinfunction "B_13") (pintype "input"))
      (node (ref "B-IN") (pin "1") (pinfunction "1_1") (pintype "passive"))
      (node (ref "CMP-H") (pin "1") (pinfunction "Q3_1") (pintype "input"))
      (node (ref "NOT-1") (pin "3") (pinfunction "A_3") (pintype "input"))
      (node (ref "OR-1") (pin "13") (pinfunction "B_13") (pintype "input"))
      (node (ref "XOR-1") (pin "13") (pinfunction "B_13") (pintype "input"))
    )
    (net (code "30") (name "BO-0") (class "Default")
      (node (ref "ACC-B") (pin "2") (pinfunction "A1_2") (pintype "bidirectional"))
      (node (ref "ADDER-B") (pin "18") (pinfunction "B1_18") (pintype "bidirectional"))
      (node (ref "AND-B") (pin "18") (pinfunction "B1_18") (pintype "bidirectional"))
      (node (ref "B-OUT") (pin "8") (pinfunction "8_8") (pintype "passive"))
      (node (ref "NOT-B") (pin "18") (pinfunction "B1_18") (pintype "bidirectional"))
      (node (ref "OR-B") (pin "18") (pinfunction "B1_18") (pintype "bidirectional"))
      (node (ref "XOR-B") (pin "18") (pinfunction "B1_18") (pintype "bidirectional"))
    )
    (net (code "31") (name "BO-1") (class "Default")
      (node (ref "ACC-B") (pin "3") (pinfunction "A2_3") (pintype "bidirectional"))
      (node (ref "ADDER-B") (pin "17") (pinfunction "B2_17") (pintype "bidirectional"))
      (node (ref "AND-B") (pin "17") (pinfunction "B2_17") (pintype "bidirectional"))
      (node (ref "B-OUT") (pin "7") (pinfunction "7_7") (pintype "passive"))
      (node (ref "NOT-B") (pin "17") (pinfunction "B2_17") (pintype "bidirectional"))
      (node (ref "OR-B") (pin "17") (pinfunction "B2_17") (pintype "bidirectional"))
      (node (ref "XOR-B") (pin "17") (pinfunction "B2_17") (pintype "bidirectional"))
    )
    (net (code "32") (name "BO-2") (class "Default")
      (node (ref "ACC-B") (pin "4") (pinfunction "A3_4") (pintype "bidirectional"))
      (node (ref "ADDER-B") (pin "16") (pinfunction "B3_16") (pintype "bidirectional"))
      (node (ref "AND-B") (pin "16") (pinfunction "B3_16") (pintype "bidirectional"))
      (node (ref "B-OUT") (pin "6") (pinfunction "6_6") (pintype "passive"))
      (node (ref "NOT-B") (pin "16") (pinfunction "B3_16") (pintype "bidirectional"))
      (node (ref "OR-B") (pin "16") (pinfunction "B3_16") (pintype "bidirectional"))
      (node (ref "XOR-B") (pin "16") (pinfunction "B3_16") (pintype "bidirectional"))
    )
    (net (code "33") (name "BO-3") (class "Default")
      (node (ref "ACC-B") (pin "5") (pinfunction "A4_5") (pintype "bidirectional"))
      (node (ref "ADDER-B") (pin "15") (pinfunction "B4_15") (pintype "bidirectional"))
      (node (ref "AND-B") (pin "15") (pinfunction "B4_15") (pintype "bidirectional"))
      (node (ref "B-OUT") (pin "5") (pinfunction "5_5") (pintype "passive"))
      (node (ref "NOT-B") (pin "15") (pinfunction "B4_15") (pintype "bidirectional"))
      (node (ref "OR-B") (pin "15") (pinfunction "B4_15") (pintype "bidirectional"))
      (node (ref "XOR-B") (pin "15") (pinfunction "B4_15") (pintype "bidirectional"))
    )
    (net (code "34") (name "BO-4") (class "Default")
      (node (ref "ACC-B") (pin "6") (pinfunction "A5_6") (pintype "bidirectional"))
      (node (ref "ADDER-B") (pin "14") (pinfunction "B5_14") (pintype "bidirectional"))
      (node (ref "AND-B") (pin "14") (pinfunction "B5_14") (pintype "bidirectional"))
      (node (ref "B-OUT") (pin "4") (pinfunction "4_4") (pintype "passive"))
      (node (ref "NOT-B") (pin "14") (pinfunction "B5_14") (pintype "bidirectional"))
      (node (ref "OR-B") (pin "14") (pinfunction "B5_14") (pintype "bidirectional"))
      (node (ref "XOR-B") (pin "14") (pinfunction "B5_14") (pintype "bidirectional"))
    )
    (net (code "35") (name "BO-5") (class "Default")
      (node (ref "ACC-B") (pin "7") (pinfunction "A6_7") (pintype "bidirectional"))
      (node (ref "ADDER-B") (pin "13") (pinfunction "B6_13") (pintype "bidirectional"))
      (node (ref "AND-B") (pin "13") (pinfunction "B6_13") (pintype "bidirectional"))
      (node (ref "B-OUT") (pin "3") (pinfunction "3_3") (pintype "passive"))
      (node (ref "NOT-B") (pin "13") (pinfunction "B6_13") (pintype "bidirectional"))
      (node (ref "OR-B") (pin "13") (pinfunction "B6_13") (pintype "bidirectional"))
      (node (ref "XOR-B") (pin "13") (pinfunction "B6_13") (pintype "bidirectional"))
    )
    (net (code "36") (name "BO-6") (class "Default")
      (node (ref "ACC-B") (pin "8") (pinfunction "A7_8") (pintype "bidirectional"))
      (node (ref "ADDER-B") (pin "12") (pinfunction "B7_12") (pintype "bidirectional"))
      (node (ref "AND-B") (pin "12") (pinfunction "B7_12") (pintype "bidirectional"))
      (node (ref "B-OUT") (pin "2") (pinfunction "2_2") (pintype "passive"))
      (node (ref "NOT-B") (pin "12") (pinfunction "B7_12") (pintype "bidirectional"))
      (node (ref "OR-B") (pin "12") (pinfunction "B7_12") (pintype "bidirectional"))
      (node (ref "XOR-B") (pin "12") (pinfunction "B7_12") (pintype "bidirectional"))
    )
    (net (code "37") (name "BO-7") (class "Default")
      (node (ref "ACC-B") (pin "9") (pinfunction "A8_9") (pintype "bidirectional"))
      (node (ref "ADDER-B") (pin "11") (pinfunction "B8_11") (pintype "bidirectional"))
      (node (ref "AND-B") (pin "11") (pinfunction "B8_11") (pintype "bidirectional"))
      (node (ref "B-OUT") (pin "1") (pinfunction "1_1") (pintype "passive"))
      (node (ref "NOT-B") (pin "11") (pinfunction "B8_11") (pintype "bidirectional"))
      (node (ref "OR-B") (pin "11") (pinfunction "B8_11") (pintype "bidirectional"))
      (node (ref "XOR-B") (pin "11") (pinfunction "B8_11") (pintype "bidirectional"))
    )
    (net (code "38") (name "CO") (class "Default")
      (node (ref "ADDER-H") (pin "7") (pinfunction "C0_7") (pintype "input"))
      (node (ref "ADDER-L") (pin "9") (pinfunction "C4_9") (pintype "output"))
      (node (ref "CO") (pin "2") (pinfunction "2_2") (pintype "passive"))
    )
    (net (code "39") (name "E") (class "Default")
      (node (ref "CMP-H") (pin "3") (pinfunction "PEQQ__3") (pintype "input"))
      (node (ref "CMP-L") (pin "6") (pinfunction "PEQQ_6") (pintype "output"))
      (node (ref "E") (pin "2") (pinfunction "2_2") (pintype "passive"))
    )
    (net (code "40") (name "EF") (class "Default")
      (node (ref "CMP-H") (pin "6") (pinfunction "PEQQ_6") (pintype "output"))
      (node (ref "JP2") (pin "4") (pinfunction "4_4") (pintype "passive"))
    )
    (net (code "41") (name "G") (class "Default")
      (node (ref "CMP-H") (pin "4") (pinfunction "PGTQ__4") (pintype "input"))
      (node (ref "CMP-L") (pin "5") (pinfunction "PGTQ_5") (pintype "output"))
      (node (ref "G") (pin "2") (pinfunction "2_2") (pintype "passive"))
    )
    (net (code "42") (name "GF") (class "Default")
      (node (ref "CMP-H") (pin "5") (pinfunction "PGTQ_5") (pintype "output"))
      (node (ref "JP2") (pin "2") (pinfunction "2_2") (pintype "passive"))
    )
    (net (code "43") (name "GND") (class "Default")
      (node (ref "ACC") (pin "10") (pinfunction "-UB_10") (pintype "power_in"))
      (node (ref "ACC-B") (pin "1") (pinfunction "DIR_1") (pintype "input"))
      (node (ref "ACC-B") (pin "10") (pinfunction "-UB_10") (pintype "power_in"))
      (node (ref "ADD-X-0") (pin "7") (pinfunction "-UB_7") (pintype "power_in"))
      (node (ref "ADD-X-1") (pin "7") (pinfunction "-UB_7") (pintype "power_in"))
      (node (ref "ADDER-B") (pin "10") (pinfunction "-UB_10") (pintype "power_in"))
      (node (ref "ADDER-H") (pin "8") (pinfunction "-UB_8") (pintype "power_in"))
      (node (ref "ADDER-L") (pin "8") (pinfunction "-UB_8") (pintype "power_in"))
      (node (ref "AL-0") (pin "K") (pinfunction "C_K") (pintype "passive"))
      (node (ref "AL-1") (pin "K") (pinfunction "C_K") (pintype "passive"))
      (node (ref "AL-2") (pin "K") (pinfunction "C_K") (pintype "passive"))
      (node (ref "AL-3") (pin "K") (pinfunction "C_K") (pintype "passive"))
      (node (ref "AL-4") (pin "K") (pinfunction "C_K") (pintype "passive"))
      (node (ref "AL-5") (pin "K") (pinfunction "C_K") (pintype "passive"))
      (node (ref "AL-6") (pin "K") (pinfunction "C_K") (pintype "passive"))
      (node (ref "AL-7") (pin "K") (pinfunction "C_K") (pintype "passive"))
      (node (ref "AND-0") (pin "7") (pinfunction "-UB_7") (pintype "power_in"))
      (node (ref "AND-1") (pin "7") (pinfunction "-UB_7") (pintype "power_in"))
      (node (ref "AND-B") (pin "10") (pinfunction "-UB_10") (pintype "power_in"))
      (node (ref "AND0") (pin "1") (pinfunction "1_1") (pintype "passive"))
      (node (ref "AND1") (pin "1") (pinfunction "1_1") (pintype "passive"))
      (node (ref "AND2") (pin "1") (pinfunction "1_1") (pintype "passive"))
      (node (ref "AND3") (pin "1") (pinfunction "1_1") (pintype "passive"))
      (node (ref "AND4") (pin "1") (pinfunction "1_1") (pintype "passive"))
      (node (ref "AND5") (pin "1") (pinfunction "1_1") (pintype "passive"))
      (node (ref "AND6") (pin "1") (pinfunction "1_1") (pintype "passive"))
      (node (ref "AND7") (pin "1") (pinfunction "1_1") (pintype "passive"))
      (node (ref "C1") (pin "-") (pinfunction "-_-") (pintype "passive"))
      (node (ref "C2") (pin "-") (pinfunction "-_-") (pintype "passive"))
      (node (ref "C3") (pin "-") (pinfunction "-_-") (pintype "passive"))
      (node (ref "C4") (pin "-") (pinfunction "-_-") (pintype "passive"))
      (node (ref "C5") (pin "-") (pinfunction "-_-") (pintype "passive"))
      (node (ref "C6") (pin "-") (pinfunction "-_-") (pintype "passive"))
      (node (ref "C7") (pin "-") (pinfunction "-_-") (pintype "passive"))
      (node (ref "CMP-H") (pin "8") (pinfunction "-UB_8") (pintype "power_in"))
      (node (ref "CMP-L") (pin "2") (pinfunction "PLTQ__2") (pintype "input"))
      (node (ref "CMP-L") (pin "4") (pinfunction "PGTQ__4") (pintype "input"))
      (node (ref "CMP-L") (pin "8") (pinfunction "-UB_8") (pintype "power_in"))
      (node (ref "CO") (pin "1") (pinfunction "1_1") (pintype "passive"))
      (node (ref "E") (pin "1") (pinfunction "1_1") (pintype "passive"))
      (node (ref "G") (pin "1") (pinfunction "1_1") (pintype "passive"))
      (node (ref "JP3") (pin "1") (pinfunction "1_1") (pintype "passive"))
      (node (ref "L") (pin "1") (pinfunction "1_1") (pintype "passive"))
      (node (ref "NOT-0") (pin "7") (pinfunction "-UB_7") (pintype "power_in"))
      (node (ref "NOT-1") (pin "7") (pinfunction "-UB_7") (pintype "power_in"))
      (node (ref "NOT-B") (pin "10") (pinfunction "-UB_10") (pintype "power_in"))
      (node (ref "NOT0") (pin "1") (pinfunction "1_1") (pintype "passive"))
      (node (ref "NOT1") (pin "1") (pinfunction "1_1") (pintype "passive"))
      (node (ref "NOT2") (pin "1") (pinfunction "1_1") (pintype "passive"))
      (node (ref "NOT3") (pin "1") (pinfunction "1_1") (pintype "passive"))
      (node (ref "NOT4") (pin "1") (pinfunction "1_1") (pintype "passive"))
      (node (ref "NOT5") (pin "1") (pinfunction "1_1") (pintype "passive"))
      (node (ref "NOT6") (pin "1") (pinfunction "1_1") (pintype "passive"))
      (node (ref "NOT7") (pin "1") (pinfunction "1_1") (pintype "passive"))
      (node (ref "OR-0") (pin "7") (pinfunction "-UB_7") (pintype "power_in"))
      (node (ref "OR-1") (pin "7") (pinfunction "-UB_7") (pintype "power_in"))
      (node (ref "OR-B") (pin "10") (pinfunction "-UB_10") (pintype "power_in"))
      (node (ref "OR0") (pin "1") (pinfunction "1_1") (pintype "passive"))
      (node (ref "OR1") (pin "1") (pinfunction "1_1") (pintype "passive"))
      (node (ref "OR2") (pin "1") (pinfunction "1_1") (pintype "passive"))
      (node (ref "OR3") (pin "1") (pinfunction "1_1") (pintype "passive"))
      (node (ref "OR4") (pin "1") (pinfunction "1_1") (pintype "passive"))
      (node (ref "OR5") (pin "1") (pinfunction "1_1") (pintype "passive"))
      (node (ref "OR6") (pin "1") (pinfunction "1_1") (pintype "passive"))
      (node (ref "OR7") (pin "1") (pinfunction "1_1") (pintype "passive"))
      (node (ref "S0") (pin "1") (pinfunction "1_1") (pintype "passive"))
      (node (ref "S1") (pin "1") (pinfunction "1_1") (pintype "passive"))
      (node (ref "S2") (pin "1") (pinfunction "1_1") (pintype "passive"))
      (node (ref "S3") (pin "1") (pinfunction "1_1") (pintype "passive"))
      (node (ref "S4") (pin "1") (pinfunction "1_1") (pintype "passive"))
      (node (ref "S5") (pin "1") (pinfunction "1_1") (pintype "passive"))
      (node (ref "S6") (pin "1") (pinfunction "1_1") (pintype "passive"))
      (node (ref "S7") (pin "1") (pinfunction "1_1") (pintype "passive"))
      (node (ref "T0") (pin "1") (pinfunction "1_1") (pintype "passive"))
      (node (ref "T1") (pin "1") (pinfunction "1_1") (pintype "passive"))
      (node (ref "T2") (pin "1") (pinfunction "1_1") (pintype "passive"))
      (node (ref "T3") (pin "1") (pinfunction "1_1") (pintype "passive"))
      (node (ref "T4") (pin "1") (pinfunction "1_1") (pintype "passive"))
      (node (ref "T5") (pin "1") (pinfunction "1_1") (pintype "passive"))
      (node (ref "T6") (pin "1") (pinfunction "1_1") (pintype "passive"))
      (node (ref "T7") (pin "1") (pinfunction "1_1") (pintype "passive"))
      (node (ref "XOR-0") (pin "7") (pinfunction "-UB_7") (pintype "power_in"))
      (node (ref "XOR-1") (pin "7") (pinfunction "-UB_7") (pintype "power_in"))
      (node (ref "XOR-B") (pin "10") (pinfunction "-UB_10") (pintype "power_in"))
      (node (ref "XOR0") (pin "1") (pinfunction "1_1") (pintype "passive"))
      (node (ref "XOR1") (pin "1") (pinfunction "1_1") (pintype "passive"))
      (node (ref "XOR2") (pin "1") (pinfunction "1_1") (pintype "passive"))
      (node (ref "XOR3") (pin "1") (pinfunction "1_1") (pintype "passive"))
      (node (ref "XOR4") (pin "1") (pinfunction "1_1") (pintype "passive"))
      (node (ref "XOR5") (pin "1") (pinfunction "1_1") (pintype "passive"))
      (node (ref "XOR6") (pin "1") (pinfunction "1_1") (pintype "passive"))
      (node (ref "XOR7") (pin "1") (pinfunction "1_1") (pintype "passive"))
      (node (ref "ZF-0") (pin "7") (pinfunction "-UB_7") (pintype "power_in"))
      (node (ref "ZF-1") (pin "7") (pinfunction "-UB_7") (pintype "power_in"))
    )
    (net (code "44") (name "L") (class "Default")
      (node (ref "CMP-H") (pin "2") (pinfunction "PLTQ__2") (pintype "input"))
      (node (ref "CMP-L") (pin "7") (pinfunction "PLTQ_7") (pintype "output"))
      (node (ref "L") (pin "2") (pinfunction "2_2") (pintype "passive"))
    )
    (net (code "45") (name "LF") (class "Default")
      (node (ref "CMP-H") (pin "7") (pinfunction "PLTQ_7") (pintype "output"))
      (node (ref "JP2") (pin "6") (pinfunction "6_6") (pintype "passive"))
    )
    (net (code "46") (name "NOT-0") (class "Default")
      (node (ref "NOT-0") (pin "2") (pinfunction "Y_2") (pintype "output"))
      (node (ref "NOT-B") (pin "2") (pinfunction "A1_2") (pintype "bidirectional"))
      (node (ref "NOT0") (pin "2") (pinfunction "2_2") (pintype "passive"))
    )
    (net (code "47") (name "NOT-1") (class "Default")
      (node (ref "NOT-0") (pin "4") (pinfunction "Y_4") (pintype "output"))
      (node (ref "NOT-B") (pin "3") (pinfunction "A2_3") (pintype "bidirectional"))
      (node (ref "NOT1") (pin "2") (pinfunction "2_2") (pintype "passive"))
    )
    (net (code "48") (name "NOT-2") (class "Default")
      (node (ref "NOT-0") (pin "6") (pinfunction "Y_6") (pintype "output"))
      (node (ref "NOT-B") (pin "4") (pinfunction "A3_4") (pintype "bidirectional"))
      (node (ref "NOT2") (pin "2") (pinfunction "2_2") (pintype "passive"))
    )
    (net (code "49") (name "NOT-3") (class "Default")
      (node (ref "NOT-0") (pin "8") (pinfunction "Y_8") (pintype "output"))
      (node (ref "NOT-B") (pin "5") (pinfunction "A4_5") (pintype "bidirectional"))
      (node (ref "NOT3") (pin "2") (pinfunction "2_2") (pintype "passive"))
    )
    (net (code "50") (name "NOT-4") (class "Default")
      (node (ref "NOT-0") (pin "10") (pinfunction "Y_10") (pintype "output"))
      (node (ref "NOT-B") (pin "6") (pinfunction "A5_6") (pintype "bidirectional"))
      (node (ref "NOT4") (pin "2") (pinfunction "2_2") (pintype "passive"))
    )
    (net (code "51") (name "NOT-5") (class "Default")
      (node (ref "NOT-0") (pin "12") (pinfunction "Y_12") (pintype "output"))
      (node (ref "NOT-B") (pin "7") (pinfunction "A6_7") (pintype "bidirectional"))
      (node (ref "NOT5") (pin "2") (pinfunction "2_2") (pintype "passive"))
    )
    (net (code "52") (name "NOT-6") (class "Default")
      (node (ref "NOT-1") (pin "2") (pinfunction "Y_2") (pintype "output"))
      (node (ref "NOT-B") (pin "8") (pinfunction "A7_8") (pintype "bidirectional"))
      (node (ref "NOT6") (pin "2") (pinfunction "2_2") (pintype "passive"))
    )
    (net (code "53") (name "NOT-7") (class "Default")
      (node (ref "NOT-1") (pin "4") (pinfunction "Y_4") (pintype "output"))
      (node (ref "NOT-B") (pin "9") (pinfunction "A8_9") (pintype "bidirectional"))
      (node (ref "NOT7") (pin "2") (pinfunction "2_2") (pintype "passive"))
    )
    (net (code "54") (name "NOT-B") (class "Default")
      (node (ref "JP1") (pin "6") (pinfunction "6_6") (pintype "passive"))
      (node (ref "NOT-B") (pin "19") (pinfunction "~{G}_19") (pintype "input"))
    )
    (net (code "55") (name "Net-(AL-0-PadA)") (class "Default")
      (node (ref "AL-0") (pin "A") (pinfunction "A_A") (pintype "passive"))
      (node (ref "AR-0") (pin "1") (pinfunction "1_1") (pintype "passive"))
    )
    (net (code "56") (name "Net-(AL-1-PadA)") (class "Default")
      (node (ref "AL-1") (pin "A") (pinfunction "A_A") (pintype "passive"))
      (node (ref "AR-1") (pin "1") (pinfunction "1_1") (pintype "passive"))
    )
    (net (code "57") (name "Net-(AL-2-PadA)") (class "Default")
      (node (ref "AL-2") (pin "A") (pinfunction "A_A") (pintype "passive"))
      (node (ref "AR-2") (pin "1") (pinfunction "1_1") (pintype "passive"))
    )
    (net (code "58") (name "Net-(AL-3-PadA)") (class "Default")
      (node (ref "AL-3") (pin "A") (pinfunction "A_A") (pintype "passive"))
      (node (ref "AR-3") (pin "1") (pinfunction "1_1") (pintype "passive"))
    )
    (net (code "59") (name "Net-(AL-4-PadA)") (class "Default")
      (node (ref "AL-4") (pin "A") (pinfunction "A_A") (pintype "passive"))
      (node (ref "AR-4") (pin "1") (pinfunction "1_1") (pintype "passive"))
    )
    (net (code "60") (name "Net-(AL-5-PadA)") (class "Default")
      (node (ref "AL-5") (pin "A") (pinfunction "A_A") (pintype "passive"))
      (node (ref "AR-5") (pin "1") (pinfunction "1_1") (pintype "passive"))
    )
    (net (code "61") (name "Net-(AL-6-PadA)") (class "Default")
      (node (ref "AL-6") (pin "A") (pinfunction "A_A") (pintype "passive"))
      (node (ref "AR-6") (pin "1") (pinfunction "1_1") (pintype "passive"))
    )
    (net (code "62") (name "Net-(AL-7-PadA)") (class "Default")
      (node (ref "AL-7") (pin "A") (pinfunction "A_A") (pintype "passive"))
      (node (ref "AR-7") (pin "1") (pinfunction "1_1") (pintype "passive"))
    )
    (net (code "63") (name "Net-(ZF-0C-Y)") (class "Default")
      (node (ref "ZF-0") (pin "3") (pinfunction "Y_3") (pintype "output"))
      (node (ref "ZF-1") (pin "1") (pinfunction "A_1") (pintype "input"))
    )
    (net (code "64") (name "Net-(ZF-0D-Y)") (class "Default")
      (node (ref "ZF-0") (pin "6") (pinfunction "Y_6") (pintype "output"))
      (node (ref "ZF-1") (pin "2") (pinfunction "B_2") (pintype "input"))
    )
    (net (code "65") (name "Net-(ZF-0E-Y)") (class "Default")
      (node (ref "ZF-0") (pin "8") (pinfunction "Y_8") (pintype "output"))
      (node (ref "ZF-1") (pin "4") (pinfunction "A_4") (pintype "input"))
    )
    (net (code "66") (name "Net-(ZF-0F-Y)") (class "Default")
      (node (ref "ZF-0") (pin "11") (pinfunction "Y_11") (pintype "output"))
      (node (ref "ZF-1") (pin "5") (pinfunction "B_5") (pintype "input"))
    )
    (net (code "67") (name "Net-(ZF-1C-Y)") (class "Default")
      (node (ref "ZF-1") (pin "3") (pinfunction "Y_3") (pintype "output"))
      (node (ref "ZF-1") (pin "9") (pinfunction "A_9") (pintype "input"))
    )
    (net (code "68") (name "Net-(ZF-1D-Y)") (class "Default")
      (node (ref "ZF-1") (pin "10") (pinfunction "B_10") (pintype "input"))
      (node (ref "ZF-1") (pin "6") (pinfunction "Y_6") (pintype "output"))
    )
    (net (code "69") (name "OF") (class "Default")
      (node (ref "ADDER-H") (pin "9") (pinfunction "C4_9") (pintype "output"))
      (node (ref "JP2") (pin "5") (pinfunction "5_5") (pintype "passive"))
    )
    (net (code "70") (name "OR-0") (class "Default")
      (node (ref "OR-0") (pin "3") (pinfunction "Y_3") (pintype "output"))
      (node (ref "OR-B") (pin "2") (pinfunction "A1_2") (pintype "bidirectional"))
      (node (ref "OR0") (pin "2") (pinfunction "2_2") (pintype "passive"))
    )
    (net (code "71") (name "OR-1") (class "Default")
      (node (ref "OR-0") (pin "6") (pinfunction "Y_6") (pintype "output"))
      (node (ref "OR-B") (pin "3") (pinfunction "A2_3") (pintype "bidirectional"))
      (node (ref "OR1") (pin "2") (pinfunction "2_2") (pintype "passive"))
    )
    (net (code "72") (name "OR-2") (class "Default")
      (node (ref "OR-0") (pin "8") (pinfunction "Y_8") (pintype "output"))
      (node (ref "OR-B") (pin "4") (pinfunction "A3_4") (pintype "bidirectional"))
      (node (ref "OR2") (pin "2") (pinfunction "2_2") (pintype "passive"))
    )
    (net (code "73") (name "OR-3") (class "Default")
      (node (ref "OR-0") (pin "11") (pinfunction "Y_11") (pintype "output"))
      (node (ref "OR-B") (pin "5") (pinfunction "A4_5") (pintype "bidirectional"))
      (node (ref "OR3") (pin "2") (pinfunction "2_2") (pintype "passive"))
    )
    (net (code "74") (name "OR-4") (class "Default")
      (node (ref "OR-1") (pin "3") (pinfunction "Y_3") (pintype "output"))
      (node (ref "OR-B") (pin "6") (pinfunction "A5_6") (pintype "bidirectional"))
      (node (ref "OR4") (pin "2") (pinfunction "2_2") (pintype "passive"))
    )
    (net (code "75") (name "OR-5") (class "Default")
      (node (ref "OR-1") (pin "6") (pinfunction "Y_6") (pintype "output"))
      (node (ref "OR-B") (pin "7") (pinfunction "A6_7") (pintype "bidirectional"))
      (node (ref "OR5") (pin "2") (pinfunction "2_2") (pintype "passive"))
    )
    (net (code "76") (name "OR-6") (class "Default")
      (node (ref "OR-1") (pin "8") (pinfunction "Y_8") (pintype "output"))
      (node (ref "OR-B") (pin "8") (pinfunction "A7_8") (pintype "bidirectional"))
      (node (ref "OR6") (pin "2") (pinfunction "2_2") (pintype "passive"))
    )
    (net (code "77") (name "OR-7") (class "Default")
      (node (ref "OR-1") (pin "11") (pinfunction "Y_11") (pintype "output"))
      (node (ref "OR-B") (pin "9") (pinfunction "A8_9") (pintype "bidirectional"))
      (node (ref "OR7") (pin "2") (pinfunction "2_2") (pintype "passive"))
    )
    (net (code "78") (name "OR-B") (class "Default")
      (node (ref "JP1") (pin "4") (pinfunction "4_4") (pintype "passive"))
      (node (ref "OR-B") (pin "19") (pinfunction "~{G}_19") (pintype "input"))
    )
    (net (code "79") (name "S0") (class "Default")
      (node (ref "ADDER-B") (pin "2") (pinfunction "A1_2") (pintype "bidirectional"))
      (node (ref "ADDER-L") (pin "4") (pinfunction "S1_4") (pintype "output"))
      (node (ref "S0") (pin "2") (pinfunction "2_2") (pintype "passive"))
      (node (ref "ZF-0") (pin "1") (pinfunction "A_1") (pintype "input"))
    )
    (net (code "80") (name "S1") (class "Default")
      (node (ref "ADDER-B") (pin "3") (pinfunction "A2_3") (pintype "bidirectional"))
      (node (ref "ADDER-L") (pin "1") (pinfunction "S2_1") (pintype "output"))
      (node (ref "S1") (pin "2") (pinfunction "2_2") (pintype "passive"))
      (node (ref "ZF-0") (pin "2") (pinfunction "B_2") (pintype "input"))
    )
    (net (code "81") (name "S2") (class "Default")
      (node (ref "ADDER-B") (pin "4") (pinfunction "A3_4") (pintype "bidirectional"))
      (node (ref "ADDER-L") (pin "13") (pinfunction "S3_13") (pintype "output"))
      (node (ref "S2") (pin "2") (pinfunction "2_2") (pintype "passive"))
      (node (ref "ZF-0") (pin "4") (pinfunction "A_4") (pintype "input"))
    )
    (net (code "82") (name "S3") (class "Default")
      (node (ref "ADDER-B") (pin "5") (pinfunction "A4_5") (pintype "bidirectional"))
      (node (ref "ADDER-L") (pin "10") (pinfunction "S4_10") (pintype "output"))
      (node (ref "S3") (pin "2") (pinfunction "2_2") (pintype "passive"))
      (node (ref "ZF-0") (pin "5") (pinfunction "B_5") (pintype "input"))
    )
    (net (code "83") (name "S4") (class "Default")
      (node (ref "ADDER-B") (pin "6") (pinfunction "A5_6") (pintype "bidirectional"))
      (node (ref "ADDER-H") (pin "4") (pinfunction "S1_4") (pintype "output"))
      (node (ref "S4") (pin "2") (pinfunction "2_2") (pintype "passive"))
      (node (ref "ZF-0") (pin "9") (pinfunction "A_9") (pintype "input"))
    )
    (net (code "84") (name "S5") (class "Default")
      (node (ref "ADDER-B") (pin "7") (pinfunction "A6_7") (pintype "bidirectional"))
      (node (ref "ADDER-H") (pin "1") (pinfunction "S2_1") (pintype "output"))
      (node (ref "S5") (pin "2") (pinfunction "2_2") (pintype "passive"))
      (node (ref "ZF-0") (pin "10") (pinfunction "B_10") (pintype "input"))
    )
    (net (code "85") (name "S6") (class "Default")
      (node (ref "ADDER-B") (pin "8") (pinfunction "A7_8") (pintype "bidirectional"))
      (node (ref "ADDER-H") (pin "13") (pinfunction "S3_13") (pintype "output"))
      (node (ref "S6") (pin "2") (pinfunction "2_2") (pintype "passive"))
      (node (ref "ZF-0") (pin "12") (pinfunction "A_12") (pintype "input"))
    )
    (net (code "86") (name "S7") (class "Default")
      (node (ref "ADDER-B") (pin "9") (pinfunction "A8_9") (pintype "bidirectional"))
      (node (ref "ADDER-H") (pin "10") (pinfunction "S4_10") (pintype "output"))
      (node (ref "JP2") (pin "1") (pinfunction "1_1") (pintype "passive"))
      (node (ref "S7") (pin "2") (pinfunction "2_2") (pintype "passive"))
      (node (ref "ZF-0") (pin "13") (pinfunction "B_13") (pintype "input"))
    )
    (net (code "87") (name "SUB") (class "Default")
      (node (ref "ADD-X-0") (pin "10") (pinfunction "B_10") (pintype "input"))
      (node (ref "ADD-X-0") (pin "13") (pinfunction "B_13") (pintype "input"))
      (node (ref "ADD-X-0") (pin "2") (pinfunction "B_2") (pintype "input"))
      (node (ref "ADD-X-0") (pin "5") (pinfunction "B_5") (pintype "input"))
      (node (ref "ADD-X-1") (pin "10") (pinfunction "B_10") (pintype "input"))
      (node (ref "ADD-X-1") (pin "13") (pinfunction "B_13") (pintype "input"))
      (node (ref "ADD-X-1") (pin "2") (pinfunction "B_2") (pintype "input"))
      (node (ref "ADD-X-1") (pin "5") (pinfunction "B_5") (pintype "input"))
      (node (ref "ADDER-L") (pin "7") (pinfunction "C0_7") (pintype "input"))
      (node (ref "JP1") (pin "9") (pinfunction "9_9") (pintype "passive"))
    )
    (net (code "88") (name "T0") (class "Default")
      (node (ref "ADD-X-0") (pin "3") (pinfunction "Y_3") (pintype "output"))
      (node (ref "ADDER-L") (pin "6") (pinfunction "B1_6") (pintype "input"))
      (node (ref "T0") (pin "2") (pinfunction "2_2") (pintype "passive"))
    )
    (net (code "89") (name "T1") (class "Default")
      (node (ref "ADD-X-0") (pin "6") (pinfunction "Y_6") (pintype "output"))
      (node (ref "ADDER-L") (pin "2") (pinfunction "B2_2") (pintype "input"))
      (node (ref "T1") (pin "2") (pinfunction "2_2") (pintype "passive"))
    )
    (net (code "90") (name "T2") (class "Default")
      (node (ref "ADD-X-0") (pin "8") (pinfunction "Y_8") (pintype "output"))
      (node (ref "ADDER-L") (pin "15") (pinfunction "B3_15") (pintype "input"))
      (node (ref "T2") (pin "2") (pinfunction "2_2") (pintype "passive"))
    )
    (net (code "91") (name "T3") (class "Default")
      (node (ref "ADD-X-0") (pin "11") (pinfunction "Y_11") (pintype "output"))
      (node (ref "ADDER-L") (pin "11") (pinfunction "B4_11") (pintype "input"))
      (node (ref "T3") (pin "2") (pinfunction "2_2") (pintype "passive"))
    )
    (net (code "92") (name "T4") (class "Default")
      (node (ref "ADD-X-1") (pin "3") (pinfunction "Y_3") (pintype "output"))
      (node (ref "ADDER-H") (pin "6") (pinfunction "B1_6") (pintype "input"))
      (node (ref "T4") (pin "2") (pinfunction "2_2") (pintype "passive"))
    )
    (net (code "93") (name "T5") (class "Default")
      (node (ref "ADD-X-1") (pin "6") (pinfunction "Y_6") (pintype "output"))
      (node (ref "ADDER-H") (pin "2") (pinfunction "B2_2") (pintype "input"))
      (node (ref "T5") (pin "2") (pinfunction "2_2") (pintype "passive"))
    )
    (net (code "94") (name "T6") (class "Default")
      (node (ref "ADD-X-1") (pin "8") (pinfunction "Y_8") (pintype "output"))
      (node (ref "ADDER-H") (pin "15") (pinfunction "B3_15") (pintype "input"))
      (node (ref "T6") (pin "2") (pinfunction "2_2") (pintype "passive"))
    )
    (net (code "95") (name "T7") (class "Default")
      (node (ref "ADD-X-1") (pin "11") (pinfunction "Y_11") (pintype "output"))
      (node (ref "ADDER-H") (pin "11") (pinfunction "B4_11") (pintype "input"))
      (node (ref "T7") (pin "2") (pinfunction "2_2") (pintype "passive"))
    )
    (net (code "96") (name "VCC") (class "Default")
      (node (ref "ACC") (pin "20") (pinfunction "+UB_20") (pintype "power_in"))
      (node (ref "ACC-B") (pin "20") (pinfunction "+UB_20") (pintype "power_in"))
      (node (ref "ADD-X-0") (pin "14") (pinfunction "+UB_14") (pintype "power_in"))
      (node (ref "ADD-X-1") (pin "14") (pinfunction "+UB_14") (pintype "power_in"))
      (node (ref "ADDER-B") (pin "1") (pinfunction "DIR_1") (pintype "input"))
      (node (ref "ADDER-B") (pin "20") (pinfunction "+UB_20") (pintype "power_in"))
      (node (ref "ADDER-H") (pin "16") (pinfunction "+UB_16") (pintype "power_in"))
      (node (ref "ADDER-L") (pin "16") (pinfunction "+UB_16") (pintype "power_in"))
      (node (ref "AND-0") (pin "14") (pinfunction "+UB_14") (pintype "power_in"))
      (node (ref "AND-1") (pin "14") (pinfunction "+UB_14") (pintype "power_in"))
      (node (ref "AND-B") (pin "1") (pinfunction "DIR_1") (pintype "input"))
      (node (ref "AND-B") (pin "20") (pinfunction "+UB_20") (pintype "power_in"))
      (node (ref "C1") (pin "+") (pinfunction "+_+") (pintype "passive"))
      (node (ref "C2") (pin "+") (pinfunction "+_+") (pintype "passive"))
      (node (ref "C3") (pin "+") (pinfunction "+_+") (pintype "passive"))
      (node (ref "C4") (pin "+") (pinfunction "+_+") (pintype "passive"))
      (node (ref "C5") (pin "+") (pinfunction "+_+") (pintype "passive"))
      (node (ref "C6") (pin "+") (pinfunction "+_+") (pintype "passive"))
      (node (ref "C7") (pin "+") (pinfunction "+_+") (pintype "passive"))
      (node (ref "CMP-H") (pin "16") (pinfunction "+UB_16") (pintype "power_in"))
      (node (ref "CMP-L") (pin "16") (pinfunction "+UB_16") (pintype "power_in"))
      (node (ref "CMP-L") (pin "3") (pinfunction "PEQQ__3") (pintype "input"))
      (node (ref "JP3") (pin "2") (pinfunction "2_2") (pintype "passive"))
      (node (ref "NOT-0") (pin "14") (pinfunction "+UB_14") (pintype "power_in"))
      (node (ref "NOT-1") (pin "14") (pinfunction "+UB_14") (pintype "power_in"))
      (node (ref "NOT-B") (pin "1") (pinfunction "DIR_1") (pintype "input"))
      (node (ref "NOT-B") (pin "20") (pinfunction "+UB_20") (pintype "power_in"))
      (node (ref "OR-0") (pin "14") (pinfunction "+UB_14") (pintype "power_in"))
      (node (ref "OR-1") (pin "14") (pinfunction "+UB_14") (pintype "power_in"))
      (node (ref "OR-B") (pin "1") (pinfunction "DIR_1") (pintype "input"))
      (node (ref "OR-B") (pin "20") (pinfunction "+UB_20") (pintype "power_in"))
      (node (ref "XOR-0") (pin "14") (pinfunction "+UB_14") (pintype "power_in"))
      (node (ref "XOR-1") (pin "14") (pinfunction "+UB_14") (pintype "power_in"))
      (node (ref "XOR-B") (pin "1") (pinfunction "DIR_1") (pintype "input"))
      (node (ref "XOR-B") (pin "20") (pinfunction "+UB_20") (pintype "power_in"))
      (node (ref "ZF-0") (pin "14") (pinfunction "+UB_14") (pintype "power_in"))
      (node (ref "ZF-1") (pin "14") (pinfunction "+UB_14") (pintype "power_in"))
    )
    (net (code "97") (name "XOR-0") (class "Default")
      (node (ref "XOR-0") (pin "3") (pinfunction "Y_3") (pintype "output"))
      (node (ref "XOR-B") (pin "2") (pinfunction "A1_2") (pintype "bidirectional"))
      (node (ref "XOR0") (pin "2") (pinfunction "2_2") (pintype "passive"))
    )
    (net (code "98") (name "XOR-1") (class "Default")
      (node (ref "XOR-0") (pin "6") (pinfunction "Y_6") (pintype "output"))
      (node (ref "XOR-B") (pin "3") (pinfunction "A2_3") (pintype "bidirectional"))
      (node (ref "XOR1") (pin "2") (pinfunction "2_2") (pintype "passive"))
    )
    (net (code "99") (name "XOR-2") (class "Default")
      (node (ref "XOR-0") (pin "8") (pinfunction "Y_8") (pintype "output"))
      (node (ref "XOR-B") (pin "4") (pinfunction "A3_4") (pintype "bidirectional"))
      (node (ref "XOR2") (pin "2") (pinfunction "2_2") (pintype "passive"))
    )
    (net (code "100") (name "XOR-3") (class "Default")
      (node (ref "XOR-0") (pin "11") (pinfunction "Y_11") (pintype "output"))
      (node (ref "XOR-B") (pin "5") (pinfunction "A4_5") (pintype "bidirectional"))
      (node (ref "XOR3") (pin "2") (pinfunction "2_2") (pintype "passive"))
    )
    (net (code "101") (name "XOR-4") (class "Default")
      (node (ref "XOR-1") (pin "3") (pinfunction "Y_3") (pintype "output"))
      (node (ref "XOR-B") (pin "6") (pinfunction "A5_6") (pintype "bidirectional"))
      (node (ref "XOR4") (pin "2") (pinfunction "2_2") (pintype "passive"))
    )
    (net (code "102") (name "XOR-5") (class "Default")
      (node (ref "XOR-1") (pin "6") (pinfunction "Y_6") (pintype "output"))
      (node (ref "XOR-B") (pin "7") (pinfunction "A6_7") (pintype "bidirectional"))
      (node (ref "XOR5") (pin "2") (pinfunction "2_2") (pintype "passive"))
    )
    (net (code "103") (name "XOR-6") (class "Default")
      (node (ref "XOR-1") (pin "8") (pinfunction "Y_8") (pintype "output"))
      (node (ref "XOR-B") (pin "8") (pinfunction "A7_8") (pintype "bidirectional"))
      (node (ref "XOR6") (pin "2") (pinfunction "2_2") (pintype "passive"))
    )
    (net (code "104") (name "XOR-7") (class "Default")
      (node (ref "XOR-1") (pin "11") (pinfunction "Y_11") (pintype "output"))
      (node (ref "XOR-B") (pin "9") (pinfunction "A8_9") (pintype "bidirectional"))
      (node (ref "XOR7") (pin "2") (pinfunction "2_2") (pintype "passive"))
    )
    (net (code "105") (name "XOR-B") (class "Default")
      (node (ref "JP1") (pin "8") (pinfunction "8_8") (pintype "passive"))
      (node (ref "XOR-B") (pin "19") (pinfunction "~{G}_19") (pintype "input"))
    )
    (net (code "106") (name "ZF") (class "Default")
      (node (ref "JP2") (pin "3") (pinfunction "3_3") (pintype "passive"))
      (node (ref "ZF-1") (pin "8") (pinfunction "Y_8") (pintype "output"))
    )
    (net (code "107") (name "unconnected-(JP1-Pad10)") (class "Default")
      (node (ref "JP1") (pin "10") (pinfunction "10_10") (pintype "passive"))
    )
  )
)
